# Daughter_Card_v7_fixed.net
KiCad netlist of a schematic drawn in EAGLE
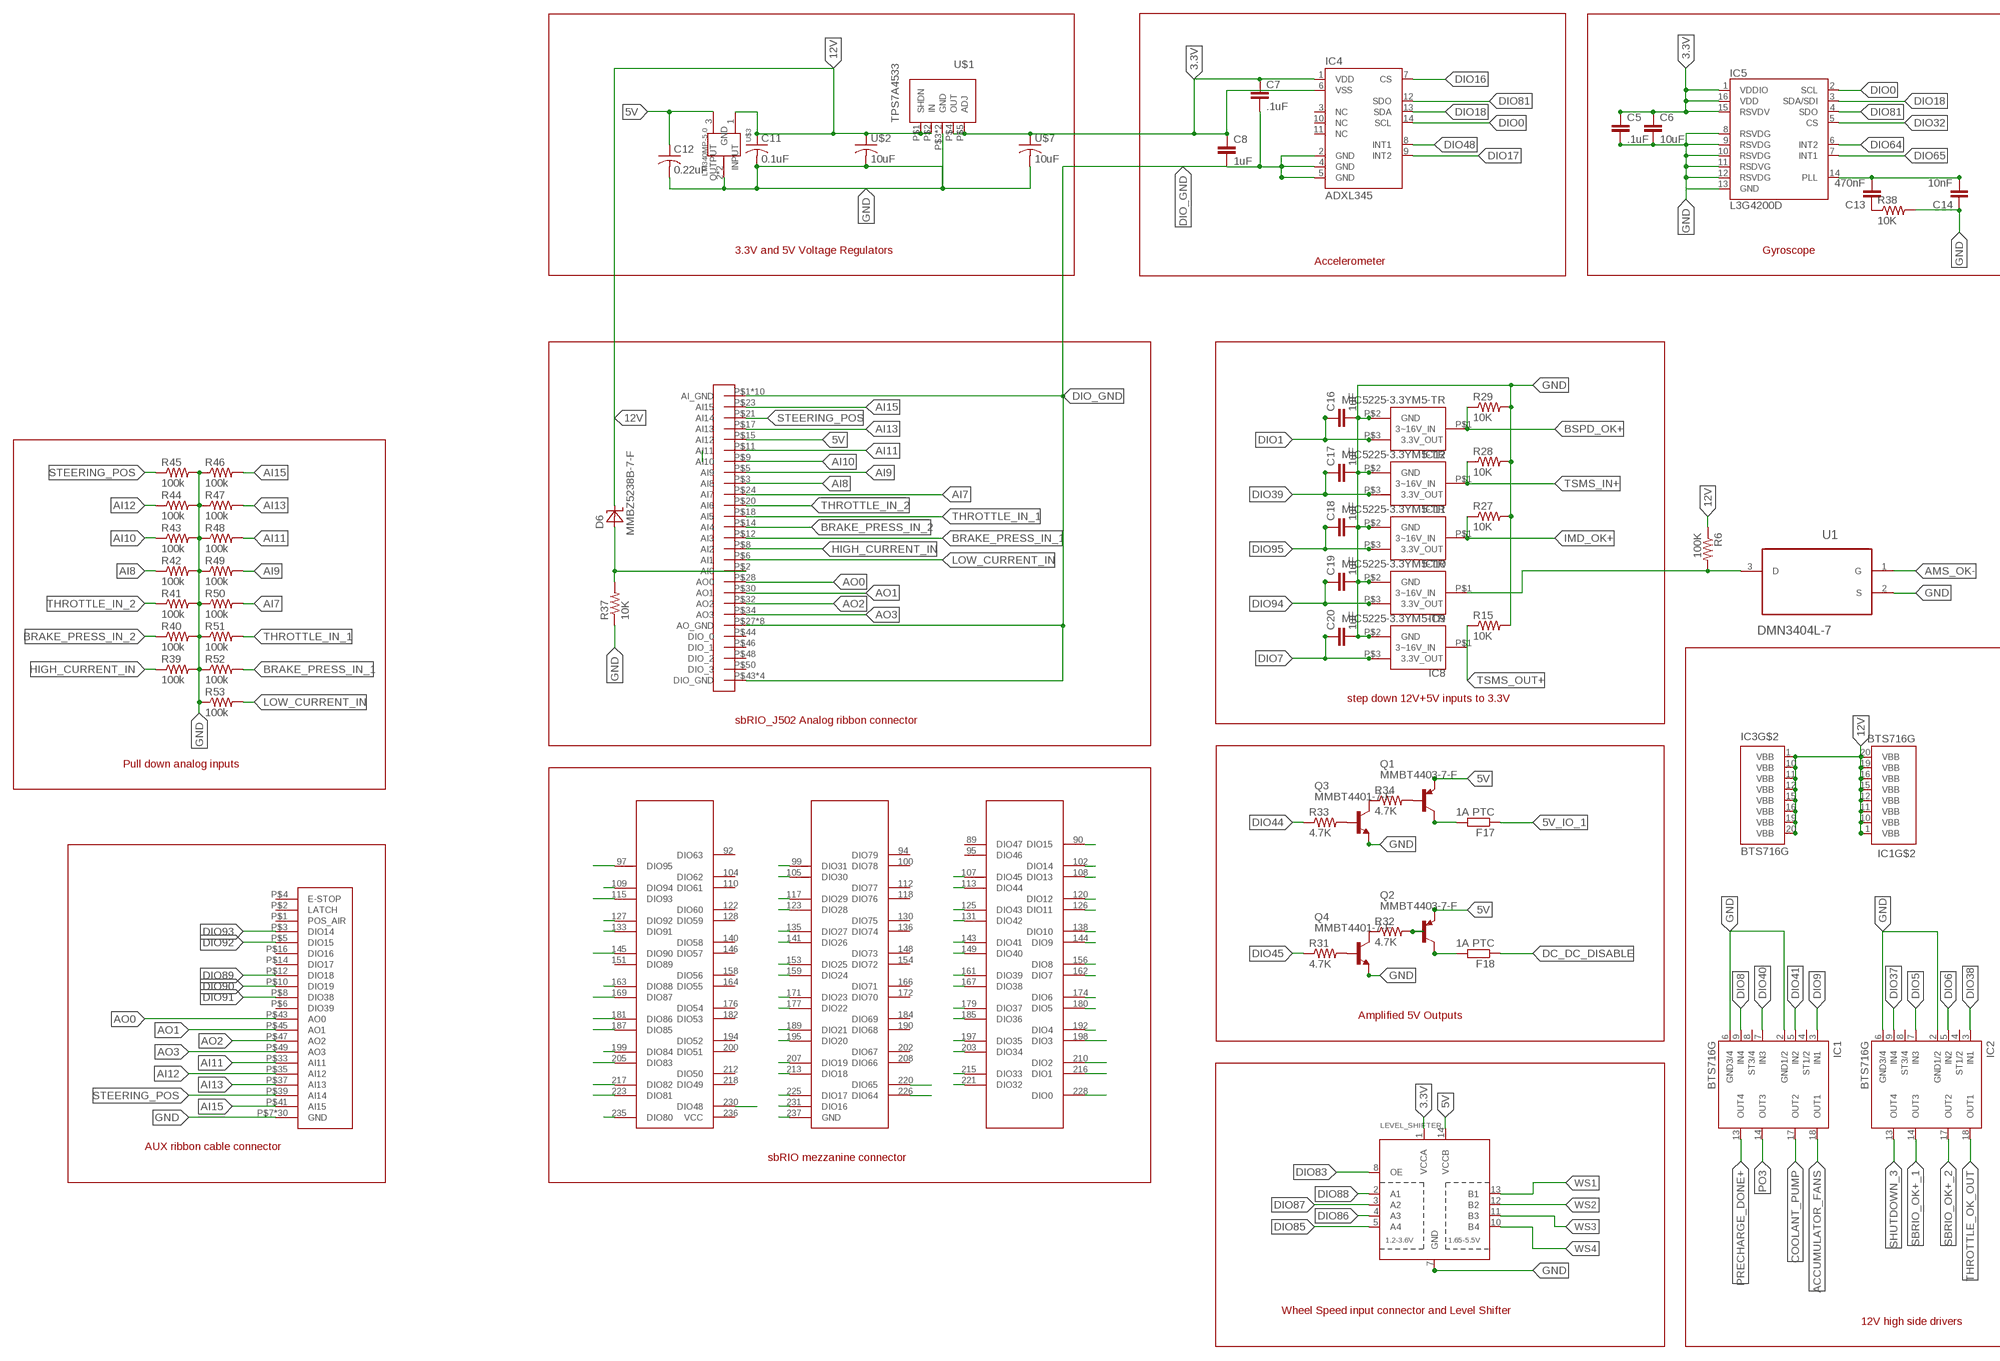
[diagram p0: schematic, sheet 1, part 1 of 2]
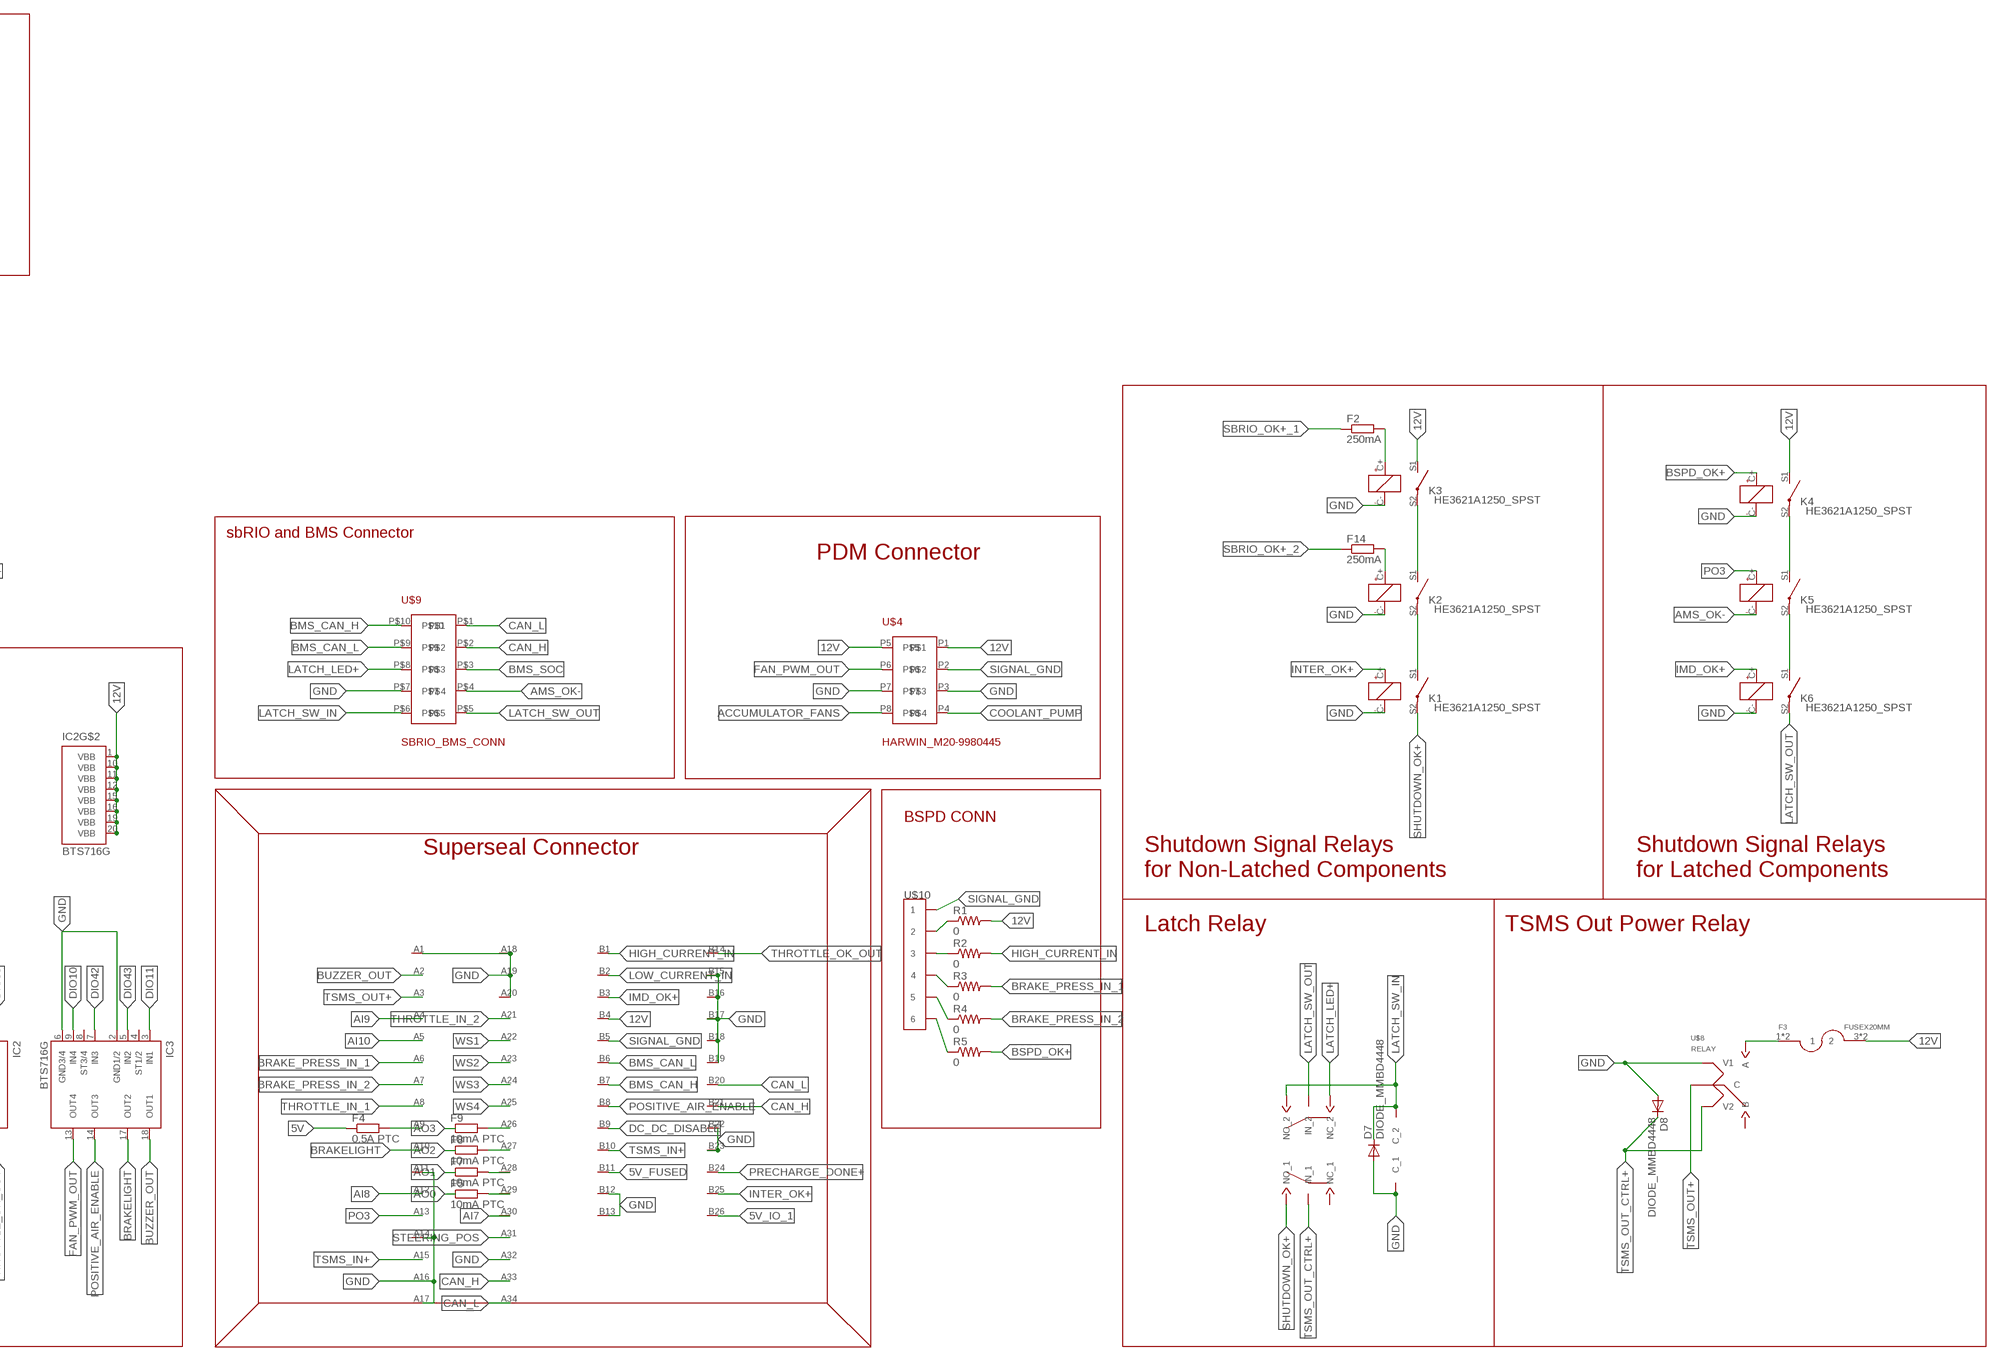
[diagram p1: schematic, sheet 1, part 2 of 2]

(export (version "E")
  (design (tool "Eeschema 10.0.6"))
  (components
    (comp (ref "C5")
      (value ".1uF")
      (footprint "eagle-import:0603-CAP")
      (libsource (lib "eagle-import") (part "CAP0603-CAP"))
    )
    (comp (ref "C6")
      (value "10uF")
      (footprint "eagle-import:0603-CAP")
      (libsource (lib "eagle-import") (part "CAP0603-CAP"))
    )
    (comp (ref "C7")
      (value ".1uF")
      (footprint "eagle-import:0603-CAP")
      (libsource (lib "eagle-import") (part "CAP0603-CAP"))
    )
    (comp (ref "C8")
      (value "1uF")
      (footprint "eagle-import:0603-CAP")
      (libsource (lib "eagle-import") (part "CAP0603-CAP"))
    )
    (comp (ref "C11")
      (value "0.1uF")
      (footprint "eagle-import:C1206")
      (libsource (lib "eagle-import") (part "C-USC1206"))
    )
    (comp (ref "C12")
      (value "0.22uF")
      (footprint "eagle-import:C1206")
      (libsource (lib "eagle-import") (part "C-USC1206"))
    )
    (comp (ref "C13")
      (value "470nF")
      (footprint "eagle-import:0603-CAP")
      (libsource (lib "eagle-import") (part "CAP0603-CAP"))
    )
    (comp (ref "C14")
      (value "10nF")
      (footprint "eagle-import:0603-CAP")
      (libsource (lib "eagle-import") (part "CAP0603-CAP"))
    )
    (comp (ref "C16")
      (value "1uF")
      (footprint "eagle-import:0603-CAP")
      (libsource (lib "eagle-import") (part "CAP0603-CAP"))
    )
    (comp (ref "C17")
      (value "1uF")
      (footprint "eagle-import:0603-CAP")
      (libsource (lib "eagle-import") (part "CAP0603-CAP"))
    )
    (comp (ref "C18")
      (value "1uF")
      (footprint "eagle-import:0603-CAP")
      (libsource (lib "eagle-import") (part "CAP0603-CAP"))
    )
    (comp (ref "C19")
      (value "1uF")
      (footprint "eagle-import:0603-CAP")
      (libsource (lib "eagle-import") (part "CAP0603-CAP"))
    )
    (comp (ref "C20")
      (value "1uF")
      (footprint "eagle-import:0603-CAP")
      (libsource (lib "eagle-import") (part "CAP0603-CAP"))
    )
    (comp (ref "D6")
      (value "MMBZ5238B-7-F")
      (footprint "eagle-import:SOT-23-3")
      (libsource (lib "eagle-import") (part "MMBZ5238B-7-F"))
    )
    (comp (ref "D7")
      (value "DIODE_MMBD4448")
      (footprint "eagle-import:SOT-23-3")
      (libsource (lib "eagle-import") (part "DIODE_MMBD4448"))
    )
    (comp (ref "D8")
      (value "DIODE_MMBD4448")
      (footprint "eagle-import:SOT-23-3")
      (libsource (lib "eagle-import") (part "DIODE_MMBD4448"))
    )
    (comp (ref "F2")
      (value "250mA")
      (footprint "eagle-import:R0603")
      (libsource (lib "eagle-import") (part "R-EU_R0603"))
    )
    (comp (ref "F3")
      (value "FUSEX20MM")
      (footprint "eagle-import:FUSE_5MM")
      (libsource (lib "eagle-import") (part "FUSEX20MM"))
    )
    (comp (ref "F4")
      (value "0.5A PTC")
      (footprint "eagle-import:R0603")
      (libsource (lib "eagle-import") (part "R-EU_R0603"))
    )
    (comp (ref "F5")
      (value "10mA PTC")
      (footprint "eagle-import:R0603")
      (libsource (lib "eagle-import") (part "R-EU_R0603"))
    )
    (comp (ref "F7")
      (value "10mA PTC")
      (footprint "eagle-import:R0603")
      (libsource (lib "eagle-import") (part "R-EU_R0603"))
    )
    (comp (ref "F8")
      (value "10mA PTC")
      (footprint "eagle-import:R0603")
      (libsource (lib "eagle-import") (part "R-EU_R0603"))
    )
    (comp (ref "F9")
      (value "10mA PTC")
      (footprint "eagle-import:R0603")
      (libsource (lib "eagle-import") (part "R-EU_R0603"))
    )
    (comp (ref "F14")
      (value "250mA")
      (footprint "eagle-import:R0603")
      (libsource (lib "eagle-import") (part "R-EU_R0603"))
    )
    (comp (ref "F17")
      (value "1A PTC")
      (footprint "eagle-import:R0603")
      (libsource (lib "eagle-import") (part "R-EU_R0603"))
    )
    (comp (ref "F18")
      (value "1A PTC")
      (footprint "eagle-import:R0603")
      (libsource (lib "eagle-import") (part "R-EU_R0603"))
    )
    (comp (ref "IC1")
      (value "BTS716G")
      (footprint "eagle-import:PG-DSO-20")
      (libsource (lib "eagle-import") (part "BTS716G"))
    )
    (comp (ref "IC2")
      (value "BTS716G")
      (footprint "eagle-import:PG-DSO-20")
      (libsource (lib "eagle-import") (part "BTS716G"))
    )
    (comp (ref "IC3")
      (value "BTS716G")
      (footprint "eagle-import:PG-DSO-20")
      (libsource (lib "eagle-import") (part "BTS716G"))
    )
    (comp (ref "IC4")
      (value "ADXL345")
      (footprint "eagle-import:LGA14")
      (libsource (lib "eagle-import") (part "ADXL345"))
    )
    (comp (ref "IC5")
      (value "L3G4200D")
      (footprint "eagle-import:LGA16-4X4")
      (libsource (lib "eagle-import") (part "L3G4200D"))
    )
    (comp (ref "IC8")
      (value "MIC5225-3.3YM5-TR")
      (footprint "eagle-import:SOT-23-3")
      (libsource (lib "eagle-import") (part "MIC5225-3.3YM5-TR"))
    )
    (comp (ref "IC9")
      (value "MIC5225-3.3YM5-TR")
      (footprint "eagle-import:SOT-23-3")
      (libsource (lib "eagle-import") (part "MIC5225-3.3YM5-TR"))
    )
    (comp (ref "IC10")
      (value "MIC5225-3.3YM5-TR")
      (footprint "eagle-import:SOT-23-3")
      (libsource (lib "eagle-import") (part "MIC5225-3.3YM5-TR"))
    )
    (comp (ref "IC11")
      (value "MIC5225-3.3YM5-TR")
      (footprint "eagle-import:SOT-23-3")
      (libsource (lib "eagle-import") (part "MIC5225-3.3YM5-TR"))
    )
    (comp (ref "IC12")
      (value "MIC5225-3.3YM5-TR")
      (footprint "eagle-import:SOT-23-3")
      (libsource (lib "eagle-import") (part "MIC5225-3.3YM5-TR"))
    )
    (comp (ref "K1")
      (value "HE3621A1250_SPST")
      (footprint "eagle-import:HE3621A1250_SPST")
      (libsource (lib "eagle-import") (part "HE3621A1250_SPST"))
    )
    (comp (ref "K2")
      (value "HE3621A1250_SPST")
      (footprint "eagle-import:HE3621A1250_SPST")
      (libsource (lib "eagle-import") (part "HE3621A1250_SPST"))
    )
    (comp (ref "K3")
      (value "HE3621A1250_SPST")
      (footprint "eagle-import:HE3621A1250_SPST")
      (libsource (lib "eagle-import") (part "HE3621A1250_SPST"))
    )
    (comp (ref "K4")
      (value "HE3621A1250_SPST")
      (footprint "eagle-import:HE3621A1250_SPST")
      (libsource (lib "eagle-import") (part "HE3621A1250_SPST"))
    )
    (comp (ref "K5")
      (value "HE3621A1250_SPST")
      (footprint "eagle-import:HE3621A1250_SPST")
      (libsource (lib "eagle-import") (part "HE3621A1250_SPST"))
    )
    (comp (ref "K6")
      (value "HE3621A1250_SPST")
      (footprint "eagle-import:HE3621A1250_SPST")
      (libsource (lib "eagle-import") (part "HE3621A1250_SPST"))
    )
    (comp (ref "LATCH_U7")
      (value "JW2SN-DC12V")
      (footprint "eagle-import:DPDT_JW2_FORM_C")
      (libsource (lib "eagle-import") (part "JW2SN-DC12V"))
    )
    (comp (ref "LEVEL_SHIFTER")
      (value "TXB0104PWR")
      (footprint "eagle-import:TSSOP14")
      (libsource (lib "eagle-import") (part "TXB0104PWR"))
    )
    (comp (ref "Q1")
      (value "MMBT4403-7-F")
      (footprint "eagle-import:SOT-23-3")
      (libsource (lib "eagle-import") (part "MMBT4403-7-F"))
    )
    (comp (ref "Q2")
      (value "MMBT4403-7-F")
      (footprint "eagle-import:SOT-23-3")
      (libsource (lib "eagle-import") (part "MMBT4403-7-F"))
    )
    (comp (ref "Q3")
      (value "MMBT4401-7-F")
      (footprint "eagle-import:SOT-23-3")
      (libsource (lib "eagle-import") (part "MMBT4401-7-F"))
    )
    (comp (ref "Q4")
      (value "MMBT4401-7-F")
      (footprint "eagle-import:SOT-23-3")
      (libsource (lib "eagle-import") (part "MMBT4401-7-F"))
    )
    (comp (ref "R1")
      (value "0")
      (footprint "eagle-import:M0805")
      (libsource (lib "eagle-import") (part "resistor_R-US_M0805"))
    )
    (comp (ref "R2")
      (value "0")
      (footprint "eagle-import:M0805")
      (libsource (lib "eagle-import") (part "resistor_R-US_M0805"))
    )
    (comp (ref "R3")
      (value "0")
      (footprint "eagle-import:M0805")
      (libsource (lib "eagle-import") (part "resistor_R-US_M0805"))
    )
    (comp (ref "R4")
      (value "0")
      (footprint "eagle-import:M0805")
      (libsource (lib "eagle-import") (part "resistor_R-US_M0805"))
    )
    (comp (ref "R5")
      (value "0")
      (footprint "eagle-import:M0805")
      (libsource (lib "eagle-import") (part "resistor_R-US_M0805"))
    )
    (comp (ref "R6")
      (value "100K")
      (footprint "eagle-import:R0603")
      (libsource (lib "eagle-import") (part "R-US_R0603"))
    )
    (comp (ref "R15")
      (value "10K")
      (footprint "eagle-import:R0603")
      (libsource (lib "eagle-import") (part "resistor_R-US_R0603"))
    )
    (comp (ref "R27")
      (value "10K")
      (footprint "eagle-import:R0603")
      (libsource (lib "eagle-import") (part "resistor_R-US_R0603"))
    )
    (comp (ref "R28")
      (value "10K")
      (footprint "eagle-import:R0603")
      (libsource (lib "eagle-import") (part "resistor_R-US_R0603"))
    )
    (comp (ref "R29")
      (value "10K")
      (footprint "eagle-import:R0603")
      (libsource (lib "eagle-import") (part "resistor_R-US_R0603"))
    )
    (comp (ref "R31")
      (value "4.7K")
      (footprint "eagle-import:R0603")
      (libsource (lib "eagle-import") (part "resistor_R-US_R0603"))
    )
    (comp (ref "R32")
      (value "4.7K")
      (footprint "eagle-import:R0603")
      (libsource (lib "eagle-import") (part "resistor_R-US_R0603"))
    )
    (comp (ref "R33")
      (value "4.7K")
      (footprint "eagle-import:R0603")
      (libsource (lib "eagle-import") (part "resistor_R-US_R0603"))
    )
    (comp (ref "R34")
      (value "4.7K")
      (footprint "eagle-import:R0603")
      (libsource (lib "eagle-import") (part "resistor_R-US_R0603"))
    )
    (comp (ref "R37")
      (value "10K")
      (footprint "eagle-import:R0603")
      (libsource (lib "eagle-import") (part "resistor_R-US_R0603"))
    )
    (comp (ref "R38")
      (value "10K")
      (footprint "eagle-import:R0603")
      (libsource (lib "eagle-import") (part "resistor_R-US_R0603"))
    )
    (comp (ref "R39")
      (value "100k")
      (footprint "eagle-import:R0603")
      (libsource (lib "eagle-import") (part "resistor_R-US_R0603"))
    )
    (comp (ref "R40")
      (value "100k")
      (footprint "eagle-import:R0603")
      (libsource (lib "eagle-import") (part "resistor_R-US_R0603"))
    )
    (comp (ref "R41")
      (value "100k")
      (footprint "eagle-import:R0603")
      (libsource (lib "eagle-import") (part "resistor_R-US_R0603"))
    )
    (comp (ref "R42")
      (value "100k")
      (footprint "eagle-import:R0603")
      (libsource (lib "eagle-import") (part "resistor_R-US_R0603"))
    )
    (comp (ref "R43")
      (value "100k")
      (footprint "eagle-import:R0603")
      (libsource (lib "eagle-import") (part "resistor_R-US_R0603"))
    )
    (comp (ref "R44")
      (value "100k")
      (footprint "eagle-import:R0603")
      (libsource (lib "eagle-import") (part "resistor_R-US_R0603"))
    )
    (comp (ref "R45")
      (value "100k")
      (footprint "eagle-import:R0603")
      (libsource (lib "eagle-import") (part "resistor_R-US_R0603"))
    )
    (comp (ref "R46")
      (value "100k")
      (footprint "eagle-import:R0603")
      (libsource (lib "eagle-import") (part "resistor_R-US_R0603"))
    )
    (comp (ref "R47")
      (value "100k")
      (footprint "eagle-import:R0603")
      (libsource (lib "eagle-import") (part "resistor_R-US_R0603"))
    )
    (comp (ref "R48")
      (value "100k")
      (footprint "eagle-import:R0603")
      (libsource (lib "eagle-import") (part "resistor_R-US_R0603"))
    )
    (comp (ref "R49")
      (value "100k")
      (footprint "eagle-import:R0603")
      (libsource (lib "eagle-import") (part "resistor_R-US_R0603"))
    )
    (comp (ref "R50")
      (value "100k")
      (footprint "eagle-import:R0603")
      (libsource (lib "eagle-import") (part "resistor_R-US_R0603"))
    )
    (comp (ref "R51")
      (value "100k")
      (footprint "eagle-import:R0603")
      (libsource (lib "eagle-import") (part "resistor_R-US_R0603"))
    )
    (comp (ref "R52")
      (value "100k")
      (footprint "eagle-import:R0603")
      (libsource (lib "eagle-import") (part "resistor_R-US_R0603"))
    )
    (comp (ref "R53")
      (value "100k")
      (footprint "eagle-import:R0603")
      (libsource (lib "eagle-import") (part "resistor_R-US_R0603"))
    )
    (comp (ref "SBRIO_ANALOG")
      (value "SBRIO_MIO")
      (footprint "eagle-import:SBRIO_J502_J503")
      (libsource (lib "eagle-import") (part "SBRIO_MIO"))
    )
    (comp (ref "SBRIO_AUX")
      (value "SBRIO_AUX")
      (footprint "eagle-import:SBRIO_J502_J503")
      (libsource (lib "eagle-import") (part "SBRIO_AUX"))
    )
    (comp (ref "SBRIO_MEZZANINE")
      (value "SBRIO_RMC")
      (footprint "eagle-import:SEAM-40-XX.X-XX-06-X-A")
      (libsource (lib "eagle-import") (part "SBRIO_RMC"))
    )
    (comp (ref "U$1")
      (value "TPS7A4533")
      (footprint "eagle-import:TPS7A4533")
      (libsource (lib "eagle-import") (part "TPS7A4533"))
    )
    (comp (ref "U$2")
      (value "10uF")
      (footprint "eagle-import:C1206")
      (libsource (lib "eagle-import") (part "C-USC1206"))
    )
    (comp (ref "U$3")
      (value "LM340MP-5.0")
      (footprint "eagle-import:SOT-223-4")
      (libsource (lib "eagle-import") (part "LM340MP-5.0"))
    )
    (comp (ref "U$4")
      (value "HARWIN_M20-9980445")
      (footprint "eagle-import:HARWIN_M20-9980445")
      (libsource (lib "eagle-import") (part "HARWIN_M20-9980445"))
    )
    (comp (ref "U$6")
      (value "SUPERSEAL1.0_60POS")
      (footprint "eagle-import:SUPERSEAL1.0_60POS")
      (libsource (lib "eagle-import") (part "SUPERSEAL1.0_60POS"))
    )
    (comp (ref "U$7")
      (value "10uF")
      (footprint "eagle-import:C1206")
      (libsource (lib "eagle-import") (part "C-USC1206"))
    )
    (comp (ref "U$8")
      (value "RELAY")
      (footprint "eagle-import:RELAY")
      (libsource (lib "eagle-import") (part "RELAY"))
    )
    (comp (ref "U$9")
      (value "SBRIO_BMS_CONN")
      (footprint "eagle-import:SBRIO_W")
      (libsource (lib "eagle-import") (part "SBRIO_BMS_CONN"))
    )
    (comp (ref "U$10")
      (value "SULLINS_1MM_6P_HEADER")
      (footprint "eagle-import:SULLINS_1MM_HEADER")
      (libsource (lib "eagle-import") (part "SULLINS_1MM_6P_HEADER"))
    )
    (comp (ref "U1")
      (value "DMN3404L-7")
      (footprint "eagle-import:SOT95P235X112-3N")
      (libsource (lib "eagle-import") (part "DMN3404L-7"))
    )
  )
  (nets
    (net (code "1") (name "/VCC") (class "Default")
      (node (ref "SBRIO_MEZZANINE") (pin "236") (pinfunction "VCC_236") (pintype "power_in"))
    )
    (net (code "2") (name "3.3V") (class "Default")
      (node (ref "C5") (pin "1") (pinfunction "1_1") (pintype "passive"))
      (node (ref "C6") (pin "1") (pinfunction "1_1") (pintype "passive"))
      (node (ref "C7") (pin "1") (pinfunction "1_1") (pintype "passive"))
      (node (ref "C8") (pin "1") (pinfunction "1_1") (pintype "passive"))
      (node (ref "IC4") (pin "1") (pinfunction "VDD_1") (pintype "bidirectional"))
      (node (ref "IC4") (pin "6") (pinfunction "VSS_6") (pintype "bidirectional"))
      (node (ref "IC5") (pin "1") (pinfunction "VDDIO_1") (pintype "bidirectional"))
      (node (ref "IC5") (pin "15") (pinfunction "RSVDV_15") (pintype "bidirectional"))
      (node (ref "IC5") (pin "16") (pinfunction "VDD_16") (pintype "bidirectional"))
      (node (ref "LEVEL_SHIFTER") (pin "1") (pinfunction "VCCA_1") (pintype "bidirectional"))
      (node (ref "U$1") (pin "P$4") (pinfunction "OUT_P$4") (pintype "bidirectional"))
      (node (ref "U$1") (pin "P$5") (pinfunction "ADJ_P$5") (pintype "bidirectional"))
      (node (ref "U$7") (pin "1") (pinfunction "1_1") (pintype "passive"))
    )
    (net (code "3") (name "5V") (class "Default")
      (node (ref "C12") (pin "1") (pinfunction "1_1") (pintype "passive"))
      (node (ref "F4") (pin "1") (pinfunction "1_1") (pintype "passive"))
      (node (ref "LEVEL_SHIFTER") (pin "14") (pinfunction "VCCB_14") (pintype "bidirectional"))
      (node (ref "Q1") (pin "P$3") (pinfunction "E_P$3") (pintype "passive"))
      (node (ref "Q2") (pin "P$3") (pinfunction "E_P$3") (pintype "passive"))
      (node (ref "SBRIO_ANALOG") (pin "P$15") (pinfunction "AI12_P$15") (pintype "input"))
      (node (ref "U$3") (pin "3") (pinfunction "OUTPUT_3") (pintype "bidirectional"))
    )
    (net (code "4") (name "5V_FUSED") (class "Default")
      (node (ref "F4") (pin "2") (pinfunction "2_2") (pintype "passive"))
      (node (ref "U$6") (pin "A9") (pinfunction "A9_A9") (pintype "bidirectional"))
      (node (ref "U$6") (pin "B11") (pinfunction "B11_B11") (pintype "bidirectional"))
    )
    (net (code "5") (name "5V_IO_1") (class "Default")
      (node (ref "F17") (pin "1") (pinfunction "1_1") (pintype "passive"))
      (node (ref "U$6") (pin "B26") (pinfunction "B26_B26") (pintype "bidirectional"))
    )
    (net (code "6") (name "12V") (class "Default")
      (node (ref "C11") (pin "1") (pinfunction "1_1") (pintype "passive"))
      (node (ref "D6") (pin "P$1") (pinfunction "C_P$1") (pintype "passive"))
      (node (ref "F3") (pin "3") (pinfunction "2_3") (pintype "bidirectional"))
      (node (ref "F3") (pin "4") (pinfunction "2_4") (pintype "bidirectional"))
      (node (ref "IC1") (pin "1") (pinfunction "VBB_1") (pintype "power_in"))
      (node (ref "IC1") (pin "10") (pinfunction "VBB_10") (pintype "power_in"))
      (node (ref "IC1") (pin "11") (pinfunction "VBB_11") (pintype "power_in"))
      (node (ref "IC1") (pin "12") (pinfunction "VBB_12") (pintype "power_in"))
      (node (ref "IC1") (pin "15") (pinfunction "VBB_15") (pintype "power_in"))
      (node (ref "IC1") (pin "16") (pinfunction "VBB_16") (pintype "power_in"))
      (node (ref "IC1") (pin "19") (pinfunction "VBB_19") (pintype "power_in"))
      (node (ref "IC1") (pin "20") (pinfunction "VBB_20") (pintype "power_in"))
      (node (ref "IC2") (pin "1") (pinfunction "VBB_1") (pintype "power_in"))
      (node (ref "IC2") (pin "10") (pinfunction "VBB_10") (pintype "power_in"))
      (node (ref "IC2") (pin "11") (pinfunction "VBB_11") (pintype "power_in"))
      (node (ref "IC2") (pin "12") (pinfunction "VBB_12") (pintype "power_in"))
      (node (ref "IC2") (pin "15") (pinfunction "VBB_15") (pintype "power_in"))
      (node (ref "IC2") (pin "16") (pinfunction "VBB_16") (pintype "power_in"))
      (node (ref "IC2") (pin "19") (pinfunction "VBB_19") (pintype "power_in"))
      (node (ref "IC2") (pin "20") (pinfunction "VBB_20") (pintype "power_in"))
      (node (ref "IC3") (pin "1") (pinfunction "VBB_1") (pintype "power_in"))
      (node (ref "IC3") (pin "10") (pinfunction "VBB_10") (pintype "power_in"))
      (node (ref "IC3") (pin "11") (pinfunction "VBB_11") (pintype "power_in"))
      (node (ref "IC3") (pin "12") (pinfunction "VBB_12") (pintype "power_in"))
      (node (ref "IC3") (pin "15") (pinfunction "VBB_15") (pintype "power_in"))
      (node (ref "IC3") (pin "16") (pinfunction "VBB_16") (pintype "power_in"))
      (node (ref "IC3") (pin "19") (pinfunction "VBB_19") (pintype "power_in"))
      (node (ref "IC3") (pin "20") (pinfunction "VBB_20") (pintype "power_in"))
      (node (ref "K3") (pin "S1") (pinfunction "SW_1_S1") (pintype "passive"))
      (node (ref "K4") (pin "S1") (pinfunction "SW_1_S1") (pintype "passive"))
      (node (ref "R1") (pin "2") (pinfunction "2_2") (pintype "passive"))
      (node (ref "R6") (pin "1") (pinfunction "1_1") (pintype "passive"))
      (node (ref "U$1") (pin "P$1") (pinfunction "SHDN_P$1") (pintype "bidirectional"))
      (node (ref "U$1") (pin "P$2") (pinfunction "IN_P$2") (pintype "bidirectional"))
      (node (ref "U$2") (pin "1") (pinfunction "1_1") (pintype "passive"))
      (node (ref "U$3") (pin "1") (pinfunction "INPUT_1") (pintype "bidirectional"))
      (node (ref "U$4") (pin "P1") (pinfunction "P$1_P1") (pintype "bidirectional"))
      (node (ref "U$4") (pin "P5") (pinfunction "P$5_P5") (pintype "bidirectional"))
      (node (ref "U$6") (pin "B4") (pinfunction "B4_B4") (pintype "bidirectional"))
    )
    (net (code "7") (name "ACCUMULATOR_FANS") (class "Default")
      (node (ref "IC1") (pin "18") (pinfunction "OUT1_18") (pintype "output"))
      (node (ref "U$4") (pin "P8") (pinfunction "P$8_P8") (pintype "bidirectional"))
    )
    (net (code "8") (name "AI7") (class "Default")
      (node (ref "R50") (pin "2") (pinfunction "2_2") (pintype "passive"))
      (node (ref "SBRIO_ANALOG") (pin "P$24") (pinfunction "AI7_P$24") (pintype "input"))
      (node (ref "U$6") (pin "A30") (pinfunction "A30_A30") (pintype "bidirectional"))
    )
    (net (code "9") (name "AI8") (class "Default")
      (node (ref "R42") (pin "1") (pinfunction "1_1") (pintype "passive"))
      (node (ref "SBRIO_ANALOG") (pin "P$3") (pinfunction "AI8_P$3") (pintype "input"))
      (node (ref "U$6") (pin "A12") (pinfunction "A12_A12") (pintype "bidirectional"))
    )
    (net (code "10") (name "AI9") (class "Default")
      (node (ref "R49") (pin "2") (pinfunction "2_2") (pintype "passive"))
      (node (ref "SBRIO_ANALOG") (pin "P$5") (pinfunction "AI9_P$5") (pintype "input"))
      (node (ref "U$6") (pin "A4") (pinfunction "A4_A4") (pintype "bidirectional"))
    )
    (net (code "11") (name "AI10") (class "Default")
      (node (ref "R43") (pin "1") (pinfunction "1_1") (pintype "passive"))
      (node (ref "SBRIO_ANALOG") (pin "P$9") (pinfunction "AI10_P$9") (pintype "input"))
      (node (ref "U$6") (pin "A5") (pinfunction "A5_A5") (pintype "bidirectional"))
    )
    (net (code "12") (name "AI11") (class "Default")
      (node (ref "R48") (pin "2") (pinfunction "2_2") (pintype "passive"))
      (node (ref "SBRIO_ANALOG") (pin "P$11") (pinfunction "AI11_P$11") (pintype "input"))
      (node (ref "SBRIO_AUX") (pin "P$33") (pinfunction "AI11_P$33") (pintype "bidirectional"))
    )
    (net (code "13") (name "AI12") (class "Default")
      (node (ref "R44") (pin "1") (pinfunction "1_1") (pintype "passive"))
      (node (ref "SBRIO_AUX") (pin "P$35") (pinfunction "AI12_P$35") (pintype "bidirectional"))
    )
    (net (code "14") (name "AI13") (class "Default")
      (node (ref "R47") (pin "2") (pinfunction "2_2") (pintype "passive"))
      (node (ref "SBRIO_ANALOG") (pin "P$17") (pinfunction "AI13_P$17") (pintype "input"))
      (node (ref "SBRIO_AUX") (pin "P$37") (pinfunction "AI13_P$37") (pintype "bidirectional"))
    )
    (net (code "15") (name "AI15") (class "Default")
      (node (ref "R46") (pin "2") (pinfunction "2_2") (pintype "passive"))
      (node (ref "SBRIO_ANALOG") (pin "P$23") (pinfunction "AI15_P$23") (pintype "input"))
      (node (ref "SBRIO_AUX") (pin "P$41") (pinfunction "AI15_P$41") (pintype "bidirectional"))
    )
    (net (code "16") (name "AMS_OK-") (class "Default")
      (node (ref "K5") (pin "C-") (pinfunction "C-_C-") (pintype "passive"))
      (node (ref "U$9") (pin "P$4") (pinfunction "P$4_P$4") (pintype "bidirectional"))
      (node (ref "U1") (pin "1") (pinfunction "G_1") (pintype "input"))
    )
    (net (code "17") (name "AO0") (class "Default")
      (node (ref "F5") (pin "1") (pinfunction "1_1") (pintype "passive"))
      (node (ref "SBRIO_ANALOG") (pin "P$28") (pinfunction "AO0_P$28") (pintype "output"))
      (node (ref "SBRIO_AUX") (pin "P$43") (pinfunction "AO0_P$43") (pintype "bidirectional"))
    )
    (net (code "18") (name "AO1") (class "Default")
      (node (ref "F7") (pin "1") (pinfunction "1_1") (pintype "passive"))
      (node (ref "SBRIO_ANALOG") (pin "P$30") (pinfunction "AO1_P$30") (pintype "output"))
      (node (ref "SBRIO_AUX") (pin "P$45") (pinfunction "AO1_P$45") (pintype "bidirectional"))
    )
    (net (code "19") (name "AO2") (class "Default")
      (node (ref "F8") (pin "1") (pinfunction "1_1") (pintype "passive"))
      (node (ref "SBRIO_ANALOG") (pin "P$32") (pinfunction "AO2_P$32") (pintype "output"))
      (node (ref "SBRIO_AUX") (pin "P$47") (pinfunction "AO2_P$47") (pintype "bidirectional"))
    )
    (net (code "20") (name "AO3") (class "Default")
      (node (ref "F9") (pin "1") (pinfunction "1_1") (pintype "passive"))
      (node (ref "SBRIO_ANALOG") (pin "P$34") (pinfunction "AO3_P$34") (pintype "output"))
      (node (ref "SBRIO_AUX") (pin "P$49") (pinfunction "AO3_P$49") (pintype "bidirectional"))
    )
    (net (code "21") (name "BMS_CAN_H") (class "Default")
      (node (ref "U$6") (pin "B7") (pinfunction "B7_B7") (pintype "bidirectional"))
      (node (ref "U$9") (pin "P$10") (pinfunction "P$10_P$10") (pintype "bidirectional"))
    )
    (net (code "22") (name "BMS_CAN_L") (class "Default")
      (node (ref "U$6") (pin "B6") (pinfunction "B6_B6") (pintype "bidirectional"))
      (node (ref "U$9") (pin "P$9") (pinfunction "P$9_P$9") (pintype "bidirectional"))
    )
    (net (code "23") (name "BMS_SOC") (class "Default")
      (node (ref "U$9") (pin "P$3") (pinfunction "P$3_P$3") (pintype "bidirectional"))
    )
    (net (code "24") (name "BRAKELIGHT") (class "Default")
      (node (ref "IC3") (pin "17") (pinfunction "OUT2_17") (pintype "output"))
      (node (ref "U$6") (pin "A10") (pinfunction "A10_A10") (pintype "bidirectional"))
    )
    (net (code "25") (name "BRAKE_PRESS_IN_1") (class "Default")
      (node (ref "R3") (pin "2") (pinfunction "2_2") (pintype "passive"))
      (node (ref "R52") (pin "2") (pinfunction "2_2") (pintype "passive"))
      (node (ref "SBRIO_ANALOG") (pin "P$12") (pinfunction "AI3_P$12") (pintype "input"))
      (node (ref "U$6") (pin "A6") (pinfunction "A6_A6") (pintype "bidirectional"))
    )
    (net (code "26") (name "BRAKE_PRESS_IN_2") (class "Default")
      (node (ref "R4") (pin "2") (pinfunction "2_2") (pintype "passive"))
      (node (ref "R40") (pin "1") (pinfunction "1_1") (pintype "passive"))
      (node (ref "SBRIO_ANALOG") (pin "P$14") (pinfunction "AI4_P$14") (pintype "input"))
      (node (ref "U$6") (pin "A7") (pinfunction "A7_A7") (pintype "bidirectional"))
    )
    (net (code "27") (name "BSPD_OK+") (class "Default")
      (node (ref "IC12") (pin "P$1") (pinfunction "3~{16V_IN}_P$1") (pintype "bidirectional"))
      (node (ref "K4") (pin "C+") (pinfunction "C+_C+") (pintype "passive"))
      (node (ref "R29") (pin "1") (pinfunction "1_1") (pintype "passive"))
      (node (ref "R5") (pin "2") (pinfunction "2_2") (pintype "passive"))
    )
    (net (code "28") (name "BUZZER_OUT") (class "Default")
      (node (ref "IC3") (pin "18") (pinfunction "OUT1_18") (pintype "output"))
      (node (ref "U$6") (pin "A2") (pinfunction "A2_A2") (pintype "bidirectional"))
    )
    (net (code "29") (name "CAN_H") (class "Default")
      (node (ref "U$6") (pin "A33") (pinfunction "A33_A33") (pintype "bidirectional"))
      (node (ref "U$6") (pin "B21") (pinfunction "B21_B21") (pintype "bidirectional"))
      (node (ref "U$9") (pin "P$2") (pinfunction "P$2_P$2") (pintype "bidirectional"))
    )
    (net (code "30") (name "CAN_L") (class "Default")
      (node (ref "U$6") (pin "A34") (pinfunction "A34_A34") (pintype "bidirectional"))
      (node (ref "U$6") (pin "B20") (pinfunction "B20_B20") (pintype "bidirectional"))
      (node (ref "U$9") (pin "P$1") (pinfunction "P$1_P$1") (pintype "bidirectional"))
    )
    (net (code "31") (name "COOLANT_PUMP") (class "Default")
      (node (ref "IC1") (pin "17") (pinfunction "OUT2_17") (pintype "output"))
      (node (ref "U$4") (pin "P4") (pinfunction "P$4_P4") (pintype "bidirectional"))
    )
    (net (code "32") (name "DC_DC_DISABLE") (class "Default")
      (node (ref "F18") (pin "1") (pinfunction "1_1") (pintype "passive"))
      (node (ref "U$6") (pin "B9") (pinfunction "B9_B9") (pintype "bidirectional"))
    )
    (net (code "33") (name "DIO0") (class "Default")
      (node (ref "IC4") (pin "14") (pinfunction "SCL_14") (pintype "bidirectional"))
      (node (ref "IC5") (pin "2") (pinfunction "SCL_2") (pintype "bidirectional"))
      (node (ref "SBRIO_MEZZANINE") (pin "228") (pinfunction "DIO0_228") (pintype "bidirectional"))
    )
    (net (code "34") (name "DIO1") (class "Default")
      (node (ref "C16") (pin "1") (pinfunction "1_1") (pintype "passive"))
      (node (ref "IC12") (pin "P$3") (pinfunction "3.3V_OUT_P$3") (pintype "bidirectional"))
      (node (ref "SBRIO_MEZZANINE") (pin "216") (pinfunction "DIO1_216") (pintype "bidirectional"))
    )
    (net (code "35") (name "DIO5") (class "Default")
      (node (ref "IC2") (pin "7") (pinfunction "IN3_7") (pintype "input"))
      (node (ref "SBRIO_MEZZANINE") (pin "180") (pinfunction "DIO5_180") (pintype "bidirectional"))
    )
    (net (code "36") (name "DIO6") (class "Default")
      (node (ref "IC2") (pin "5") (pinfunction "IN2_5") (pintype "input"))
      (node (ref "SBRIO_MEZZANINE") (pin "174") (pinfunction "DIO6_174") (pintype "bidirectional"))
    )
    (net (code "37") (name "DIO7") (class "Default")
      (node (ref "C20") (pin "1") (pinfunction "1_1") (pintype "passive"))
      (node (ref "IC8") (pin "P$3") (pinfunction "3.3V_OUT_P$3") (pintype "bidirectional"))
      (node (ref "SBRIO_MEZZANINE") (pin "162") (pinfunction "DIO7_162") (pintype "bidirectional"))
    )
    (net (code "38") (name "DIO8") (class "Default")
      (node (ref "IC1") (pin "9") (pinfunction "IN4_9") (pintype "input"))
      (node (ref "SBRIO_MEZZANINE") (pin "156") (pinfunction "DIO8_156") (pintype "bidirectional"))
    )
    (net (code "39") (name "DIO9") (class "Default")
      (node (ref "IC1") (pin "3") (pinfunction "IN1_3") (pintype "input"))
      (node (ref "SBRIO_MEZZANINE") (pin "144") (pinfunction "DIO9_144") (pintype "bidirectional"))
    )
    (net (code "40") (name "DIO10") (class "Default")
      (node (ref "IC3") (pin "9") (pinfunction "IN4_9") (pintype "input"))
      (node (ref "SBRIO_MEZZANINE") (pin "138") (pinfunction "DIO10_138") (pintype "bidirectional"))
    )
    (net (code "41") (name "DIO11") (class "Default")
      (node (ref "IC3") (pin "3") (pinfunction "IN1_3") (pintype "input"))
      (node (ref "SBRIO_MEZZANINE") (pin "126") (pinfunction "DIO11_126") (pintype "bidirectional"))
    )
    (net (code "42") (name "DIO16") (class "Default")
      (node (ref "IC4") (pin "7") (pinfunction "CS_7") (pintype "bidirectional"))
      (node (ref "SBRIO_MEZZANINE") (pin "231") (pinfunction "DIO16_231") (pintype "bidirectional"))
    )
    (net (code "43") (name "DIO17") (class "Default")
      (node (ref "IC4") (pin "9") (pinfunction "INT2_9") (pintype "bidirectional"))
      (node (ref "SBRIO_MEZZANINE") (pin "225") (pinfunction "DIO17_225") (pintype "bidirectional"))
    )
    (net (code "44") (name "DIO18") (class "Default")
      (node (ref "IC4") (pin "13") (pinfunction "SDA_13") (pintype "bidirectional"))
      (node (ref "IC5") (pin "3") (pinfunction "SDA/SDI_3") (pintype "bidirectional"))
      (node (ref "SBRIO_MEZZANINE") (pin "213") (pinfunction "DIO18_213") (pintype "bidirectional"))
    )
    (net (code "45") (name "DIO32") (class "Default")
      (node (ref "IC5") (pin "5") (pinfunction "CS_5") (pintype "bidirectional"))
      (node (ref "SBRIO_MEZZANINE") (pin "221") (pinfunction "DIO32_221") (pintype "bidirectional"))
    )
    (net (code "46") (name "DIO37") (class "Default")
      (node (ref "IC2") (pin "9") (pinfunction "IN4_9") (pintype "input"))
      (node (ref "SBRIO_MEZZANINE") (pin "179") (pinfunction "DIO37_179") (pintype "bidirectional"))
    )
    (net (code "47") (name "DIO38") (class "Default")
      (node (ref "IC2") (pin "3") (pinfunction "IN1_3") (pintype "input"))
      (node (ref "SBRIO_MEZZANINE") (pin "167") (pinfunction "DIO38_167") (pintype "bidirectional"))
    )
    (net (code "48") (name "DIO39") (class "Default")
      (node (ref "C17") (pin "1") (pinfunction "1_1") (pintype "passive"))
      (node (ref "IC11") (pin "P$3") (pinfunction "3.3V_OUT_P$3") (pintype "bidirectional"))
      (node (ref "SBRIO_MEZZANINE") (pin "161") (pinfunction "DIO39_161") (pintype "bidirectional"))
    )
    (net (code "49") (name "DIO40") (class "Default")
      (node (ref "IC1") (pin "7") (pinfunction "IN3_7") (pintype "input"))
      (node (ref "SBRIO_MEZZANINE") (pin "149") (pinfunction "DIO40_149") (pintype "bidirectional"))
    )
    (net (code "50") (name "DIO41") (class "Default")
      (node (ref "IC1") (pin "5") (pinfunction "IN2_5") (pintype "input"))
      (node (ref "SBRIO_MEZZANINE") (pin "143") (pinfunction "DIO41_143") (pintype "bidirectional"))
    )
    (net (code "51") (name "DIO42") (class "Default")
      (node (ref "IC3") (pin "7") (pinfunction "IN3_7") (pintype "input"))
      (node (ref "SBRIO_MEZZANINE") (pin "131") (pinfunction "DIO42_131") (pintype "bidirectional"))
    )
    (net (code "52") (name "DIO43") (class "Default")
      (node (ref "IC3") (pin "5") (pinfunction "IN2_5") (pintype "input"))
      (node (ref "SBRIO_MEZZANINE") (pin "125") (pinfunction "DIO43_125") (pintype "bidirectional"))
    )
    (net (code "53") (name "DIO44") (class "Default")
      (node (ref "R33") (pin "1") (pinfunction "1_1") (pintype "passive"))
      (node (ref "SBRIO_MEZZANINE") (pin "113") (pinfunction "DIO44_113") (pintype "bidirectional"))
    )
    (net (code "54") (name "DIO45") (class "Default")
      (node (ref "R31") (pin "1") (pinfunction "1_1") (pintype "passive"))
      (node (ref "SBRIO_MEZZANINE") (pin "107") (pinfunction "DIO45_107") (pintype "bidirectional"))
    )
    (net (code "55") (name "DIO48") (class "Default")
      (node (ref "IC4") (pin "8") (pinfunction "INT1_8") (pintype "bidirectional"))
      (node (ref "SBRIO_MEZZANINE") (pin "230") (pinfunction "DIO48_230") (pintype "bidirectional"))
    )
    (net (code "56") (name "DIO64") (class "Default")
      (node (ref "IC5") (pin "6") (pinfunction "INT2_6") (pintype "bidirectional"))
      (node (ref "SBRIO_MEZZANINE") (pin "226") (pinfunction "DIO64_226") (pintype "bidirectional"))
    )
    (net (code "57") (name "DIO65") (class "Default")
      (node (ref "IC5") (pin "7") (pinfunction "INT1_7") (pintype "bidirectional"))
      (node (ref "SBRIO_MEZZANINE") (pin "220") (pinfunction "DIO65_220") (pintype "bidirectional"))
    )
    (net (code "58") (name "DIO81") (class "Default")
      (node (ref "IC4") (pin "12") (pinfunction "SDO_12") (pintype "bidirectional"))
      (node (ref "IC5") (pin "4") (pinfunction "SDO_4") (pintype "bidirectional"))
      (node (ref "SBRIO_MEZZANINE") (pin "223") (pinfunction "DIO81_223") (pintype "bidirectional"))
    )
    (net (code "59") (name "DIO83") (class "Default")
      (node (ref "LEVEL_SHIFTER") (pin "8") (pinfunction "OE_8") (pintype "bidirectional"))
      (node (ref "SBRIO_MEZZANINE") (pin "205") (pinfunction "DIO83_205") (pintype "bidirectional"))
    )
    (net (code "60") (name "DIO85") (class "Default")
      (node (ref "LEVEL_SHIFTER") (pin "5") (pinfunction "A4_5") (pintype "bidirectional"))
      (node (ref "SBRIO_MEZZANINE") (pin "187") (pinfunction "DIO85_187") (pintype "bidirectional"))
    )
    (net (code "61") (name "DIO86") (class "Default")
      (node (ref "LEVEL_SHIFTER") (pin "4") (pinfunction "A3_4") (pintype "bidirectional"))
      (node (ref "SBRIO_MEZZANINE") (pin "181") (pinfunction "DIO86_181") (pintype "bidirectional"))
    )
    (net (code "62") (name "DIO87") (class "Default")
      (node (ref "LEVEL_SHIFTER") (pin "3") (pinfunction "A2_3") (pintype "bidirectional"))
      (node (ref "SBRIO_MEZZANINE") (pin "169") (pinfunction "DIO87_169") (pintype "bidirectional"))
    )
    (net (code "63") (name "DIO88") (class "Default")
      (node (ref "LEVEL_SHIFTER") (pin "2") (pinfunction "A1_2") (pintype "bidirectional"))
      (node (ref "SBRIO_MEZZANINE") (pin "163") (pinfunction "DIO88_163") (pintype "bidirectional"))
    )
    (net (code "64") (name "DIO89") (class "Default")
      (node (ref "SBRIO_AUX") (pin "P$12") (pinfunction "DIO18_P$12") (pintype "bidirectional"))
    )
    (net (code "65") (name "DIO90") (class "Default")
      (node (ref "SBRIO_AUX") (pin "P$10") (pinfunction "DIO19_P$10") (pintype "bidirectional"))
      (node (ref "SBRIO_MEZZANINE") (pin "145") (pinfunction "DIO90_145") (pintype "bidirectional"))
    )
    (net (code "66") (name "DIO91") (class "Default")
      (node (ref "SBRIO_AUX") (pin "P$8") (pinfunction "DIO38_P$8") (pintype "bidirectional"))
      (node (ref "SBRIO_MEZZANINE") (pin "133") (pinfunction "DIO91_133") (pintype "bidirectional"))
    )
    (net (code "67") (name "DIO92") (class "Default")
      (node (ref "SBRIO_AUX") (pin "P$5") (pinfunction "DIO15_P$5") (pintype "bidirectional"))
      (node (ref "SBRIO_MEZZANINE") (pin "127") (pinfunction "DIO92_127") (pintype "bidirectional"))
    )
    (net (code "68") (name "DIO93") (class "Default")
      (node (ref "SBRIO_AUX") (pin "P$3") (pinfunction "DIO14_P$3") (pintype "bidirectional"))
      (node (ref "SBRIO_MEZZANINE") (pin "115") (pinfunction "DIO93_115") (pintype "bidirectional"))
    )
    (net (code "69") (name "DIO94") (class "Default")
      (node (ref "C19") (pin "1") (pinfunction "1_1") (pintype "passive"))
      (node (ref "IC9") (pin "P$3") (pinfunction "3.3V_OUT_P$3") (pintype "bidirectional"))
      (node (ref "SBRIO_MEZZANINE") (pin "109") (pinfunction "DIO94_109") (pintype "bidirectional"))
    )
    (net (code "70") (name "DIO95") (class "Default")
      (node (ref "C18") (pin "1") (pinfunction "1_1") (pintype "passive"))
      (node (ref "IC10") (pin "P$3") (pinfunction "3.3V_OUT_P$3") (pintype "bidirectional"))
      (node (ref "SBRIO_MEZZANINE") (pin "97") (pinfunction "DIO95_97") (pintype "bidirectional"))
    )
    (net (code "71") (name "DIO_GND") (class "Default")
      (node (ref "C7") (pin "2") (pinfunction "2_2") (pintype "passive"))
      (node (ref "C8") (pin "2") (pinfunction "2_2") (pintype "passive"))
      (node (ref "IC4") (pin "2") (pinfunction "GND_2") (pintype "bidirectional"))
      (node (ref "IC4") (pin "4") (pinfunction "GND_4") (pintype "bidirectional"))
      (node (ref "IC4") (pin "5") (pinfunction "GND_5") (pintype "bidirectional"))
      (node (ref "SBRIO_ANALOG") (pin "P$1") (pinfunction "AI_GND_P$1") (pintype "input"))
      (node (ref "SBRIO_ANALOG") (pin "P$10") (pinfunction "AI_GND_P$10") (pintype "input"))
      (node (ref "SBRIO_ANALOG") (pin "P$13") (pinfunction "AI_GND_P$13") (pintype "input"))
      (node (ref "SBRIO_ANALOG") (pin "P$16") (pinfunction "AI_GND_P$16") (pintype "input"))
      (node (ref "SBRIO_ANALOG") (pin "P$19") (pinfunction "AI_GND_P$19") (pintype "input"))
      (node (ref "SBRIO_ANALOG") (pin "P$22") (pinfunction "AI_GND_P$22") (pintype "input"))
      (node (ref "SBRIO_ANALOG") (pin "P$25") (pinfunction "AI_GND_P$25") (pintype "input"))
      (node (ref "SBRIO_ANALOG") (pin "P$26") (pinfunction "AI_GND_P$26") (pintype "input"))
      (node (ref "SBRIO_ANALOG") (pin "P$27") (pinfunction "AO_GND_P$27") (pintype "power_in"))
      (node (ref "SBRIO_ANALOG") (pin "P$29") (pinfunction "AO_GND_P$29") (pintype "power_in"))
      (node (ref "SBRIO_ANALOG") (pin "P$31") (pinfunction "AO_GND_P$31") (pintype "power_in"))
      (node (ref "SBRIO_ANALOG") (pin "P$33") (pinfunction "AO_GND_P$33") (pintype "power_in"))
      (node (ref "SBRIO_ANALOG") (pin "P$35") (pinfunction "AO_GND_P$35") (pintype "power_in"))
      (node (ref "SBRIO_ANALOG") (pin "P$37") (pinfunction "AO_GND_P$37") (pintype "power_in"))
      (node (ref "SBRIO_ANALOG") (pin "P$39") (pinfunction "AO_GND_P$39") (pintype "power_in"))
      (node (ref "SBRIO_ANALOG") (pin "P$4") (pinfunction "AI_GND_P$4") (pintype "input"))
      (node (ref "SBRIO_ANALOG") (pin "P$41") (pinfunction "AO_GND_P$41") (pintype "power_in"))
      (node (ref "SBRIO_ANALOG") (pin "P$43") (pinfunction "DIO_GND_P$43") (pintype "power_in"))
      (node (ref "SBRIO_ANALOG") (pin "P$45") (pinfunction "DIO_GND_P$45") (pintype "power_in"))
      (node (ref "SBRIO_ANALOG") (pin "P$47") (pinfunction "DIO_GND_P$47") (pintype "power_in"))
      (node (ref "SBRIO_ANALOG") (pin "P$49") (pinfunction "DIO_GND_P$49") (pintype "power_in"))
      (node (ref "SBRIO_ANALOG") (pin "P$7") (pinfunction "AI_GND_P$7") (pintype "input"))
    )
    (net (code "72") (name "FAN_PWM_OUT") (class "Default")
      (node (ref "IC3") (pin "13") (pinfunction "OUT4_13") (pintype "output"))
      (node (ref "U$4") (pin "P6") (pinfunction "P$6_P6") (pintype "bidirectional"))
    )
    (net (code "73") (name "GND") (class "Default")
      (node (ref "C11") (pin "2") (pinfunction "2_2") (pintype "passive"))
      (node (ref "C12") (pin "2") (pinfunction "2_2") (pintype "passive"))
      (node (ref "C14") (pin "1") (pinfunction "1_1") (pintype "passive"))
      (node (ref "C16") (pin "2") (pinfunction "2_2") (pintype "passive"))
      (node (ref "C17") (pin "2") (pinfunction "2_2") (pintype "passive"))
      (node (ref "C18") (pin "2") (pinfunction "2_2") (pintype "passive"))
      (node (ref "C19") (pin "2") (pinfunction "2_2") (pintype "passive"))
      (node (ref "C20") (pin "2") (pinfunction "2_2") (pintype "passive"))
      (node (ref "C5") (pin "2") (pinfunction "2_2") (pintype "passive"))
      (node (ref "C6") (pin "2") (pinfunction "2_2") (pintype "passive"))
      (node (ref "D7") (pin "P$2") (pinfunction "A_P$2") (pintype "passive"))
      (node (ref "D8") (pin "P$2") (pinfunction "A_P$2") (pintype "passive"))
      (node (ref "IC1") (pin "2") (pinfunction "GND1/2_2") (pintype "input"))
      (node (ref "IC1") (pin "6") (pinfunction "GND3/4_6") (pintype "input"))
      (node (ref "IC10") (pin "P$2") (pinfunction "GND_P$2") (pintype "bidirectional"))
      (node (ref "IC11") (pin "P$2") (pinfunction "GND_P$2") (pintype "bidirectional"))
      (node (ref "IC12") (pin "P$2") (pinfunction "GND_P$2") (pintype "bidirectional"))
      (node (ref "IC2") (pin "2") (pinfunction "GND1/2_2") (pintype "input"))
      (node (ref "IC2") (pin "6") (pinfunction "GND3/4_6") (pintype "input"))
      (node (ref "IC3") (pin "2") (pinfunction "GND1/2_2") (pintype "input"))
      (node (ref "IC3") (pin "6") (pinfunction "GND3/4_6") (pintype "input"))
      (node (ref "IC5") (pin "10") (pinfunction "RSVDG_10") (pintype "bidirectional"))
      (node (ref "IC5") (pin "11") (pinfunction "RSDVG_11") (pintype "bidirectional"))
      (node (ref "IC5") (pin "12") (pinfunction "RSVDG_12") (pintype "bidirectional"))
      (node (ref "IC5") (pin "13") (pinfunction "GND_13") (pintype "bidirectional"))
      (node (ref "IC5") (pin "8") (pinfunction "RSVDG_8") (pintype "bidirectional"))
      (node (ref "IC5") (pin "9") (pinfunction "RSVDG_9") (pintype "bidirectional"))
      (node (ref "IC8") (pin "P$2") (pinfunction "GND_P$2") (pintype "bidirectional"))
      (node (ref "IC9") (pin "P$2") (pinfunction "GND_P$2") (pintype "bidirectional"))
      (node (ref "K1") (pin "C-") (pinfunction "C-_C-") (pintype "passive"))
      (node (ref "K2") (pin "C-") (pinfunction "C-_C-") (pintype "passive"))
      (node (ref "K3") (pin "C-") (pinfunction "C-_C-") (pintype "passive"))
      (node (ref "K4") (pin "C-") (pinfunction "C-_C-") (pintype "passive"))
      (node (ref "K6") (pin "C-") (pinfunction "C-_C-") (pintype "passive"))
      (node (ref "LATCH_U7") (pin "COIL_1") (pinfunction "C_1_COIL_1") (pintype "bidirectional"))
      (node (ref "LEVEL_SHIFTER") (pin "7") (pinfunction "GND_7") (pintype "bidirectional"))
      (node (ref "Q3") (pin "P$3") (pinfunction "E_P$3") (pintype "passive"))
      (node (ref "Q4") (pin "P$3") (pinfunction "E_P$3") (pintype "passive"))
      (node (ref "R15") (pin "2") (pinfunction "2_2") (pintype "passive"))
      (node (ref "R27") (pin "2") (pinfunction "2_2") (pintype "passive"))
      (node (ref "R28") (pin "2") (pinfunction "2_2") (pintype "passive"))
      (node (ref "R29") (pin "2") (pinfunction "2_2") (pintype "passive"))
      (node (ref "R37") (pin "1") (pinfunction "1_1") (pintype "passive"))
      (node (ref "R38") (pin "2") (pinfunction "2_2") (pintype "passive"))
      (node (ref "R39") (pin "2") (pinfunction "2_2") (pintype "passive"))
      (node (ref "R40") (pin "2") (pinfunction "2_2") (pintype "passive"))
      (node (ref "R41") (pin "2") (pinfunction "2_2") (pintype "passive"))
      (node (ref "R42") (pin "2") (pinfunction "2_2") (pintype "passive"))
      (node (ref "R43") (pin "2") (pinfunction "2_2") (pintype "passive"))
      (node (ref "R44") (pin "2") (pinfunction "2_2") (pintype "passive"))
      (node (ref "R45") (pin "2") (pinfunction "2_2") (pintype "passive"))
      (node (ref "R46") (pin "1") (pinfunction "1_1") (pintype "passive"))
      (node (ref "R47") (pin "1") (pinfunction "1_1") (pintype "passive"))
      (node (ref "R48") (pin "1") (pinfunction "1_1") (pintype "passive"))
      (node (ref "R49") (pin "1") (pinfunction "1_1") (pintype "passive"))
      (node (ref "R50") (pin "1") (pinfunction "1_1") (pintype "passive"))
      (node (ref "R51") (pin "1") (pinfunction "1_1") (pintype "passive"))
      (node (ref "R52") (pin "1") (pinfunction "1_1") (pintype "passive"))
      (node (ref "R53") (pin "1") (pinfunction "1_1") (pintype "passive"))
      (node (ref "SBRIO_AUX") (pin "P$11") (pinfunction "GND_P$11") (pintype "bidirectional"))
      (node (ref "SBRIO_AUX") (pin "P$13") (pinfunction "GND_P$13") (pintype "bidirectional"))
      (node (ref "SBRIO_AUX") (pin "P$15") (pinfunction "GND_P$15") (pintype "bidirectional"))
      (node (ref "SBRIO_AUX") (pin "P$17") (pinfunction "GND_P$17") (pintype "bidirectional"))
      (node (ref "SBRIO_AUX") (pin "P$18") (pinfunction "GND_P$18") (pintype "bidirectional"))
      (node (ref "SBRIO_AUX") (pin "P$19") (pinfunction "GND_P$19") (pintype "bidirectional"))
      (node (ref "SBRIO_AUX") (pin "P$20") (pinfunction "GND_P$20") (pintype "bidirectional"))
      (node (ref "SBRIO_AUX") (pin "P$21") (pinfunction "GND_P$21") (pintype "bidirectional"))
      (node (ref "SBRIO_AUX") (pin "P$22") (pinfunction "GND_P$22") (pintype "bidirectional"))
      (node (ref "SBRIO_AUX") (pin "P$23") (pinfunction "GND_P$23") (pintype "bidirectional"))
      (node (ref "SBRIO_AUX") (pin "P$24") (pinfunction "GND_P$24") (pintype "bidirectional"))
      (node (ref "SBRIO_AUX") (pin "P$25") (pinfunction "GND_P$25") (pintype "bidirectional"))
      (node (ref "SBRIO_AUX") (pin "P$26") (pinfunction "GND_P$26") (pintype "bidirectional"))
      (node (ref "SBRIO_AUX") (pin "P$27") (pinfunction "GND_P$27") (pintype "bidirectional"))
      (node (ref "SBRIO_AUX") (pin "P$28") (pinfunction "GND_P$28") (pintype "bidirectional"))
      (node (ref "SBRIO_AUX") (pin "P$29") (pinfunction "GND_P$29") (pintype "bidirectional"))
      (node (ref "SBRIO_AUX") (pin "P$30") (pinfunction "GND_P$30") (pintype "bidirectional"))
      (node (ref "SBRIO_AUX") (pin "P$31") (pinfunction "GND_P$31") (pintype "bidirectional"))
      (node (ref "SBRIO_AUX") (pin "P$32") (pinfunction "GND_P$32") (pintype "bidirectional"))
      (node (ref "SBRIO_AUX") (pin "P$34") (pinfunction "GND_P$34") (pintype "bidirectional"))
      (node (ref "SBRIO_AUX") (pin "P$36") (pinfunction "GND_P$36") (pintype "bidirectional"))
      (node (ref "SBRIO_AUX") (pin "P$38") (pinfunction "GND_P$38") (pintype "bidirectional"))
      (node (ref "SBRIO_AUX") (pin "P$40") (pinfunction "GND_P$40") (pintype "bidirectional"))
      (node (ref "SBRIO_AUX") (pin "P$42") (pinfunction "GND_P$42") (pintype "bidirectional"))
      (node (ref "SBRIO_AUX") (pin "P$44") (pinfunction "GND_P$44") (pintype "bidirectional"))
      (node (ref "SBRIO_AUX") (pin "P$46") (pinfunction "GND_P$46") (pintype "bidirectional"))
      (node (ref "SBRIO_AUX") (pin "P$48") (pinfunction "GND_P$48") (pintype "bidirectional"))
      (node (ref "SBRIO_AUX") (pin "P$50") (pinfunction "GND_P$50") (pintype "bidirectional"))
      (node (ref "SBRIO_AUX") (pin "P$7") (pinfunction "GND_P$7") (pintype "bidirectional"))
      (node (ref "SBRIO_AUX") (pin "P$9") (pinfunction "GND_P$9") (pintype "bidirectional"))
      (node (ref "SBRIO_MEZZANINE") (pin "237") (pinfunction "GND_237") (pintype "power_in"))
      (node (ref "U$1") (pin "P$3") (pinfunction "GND_P$3") (pintype "bidirectional"))
      (node (ref "U$1") (pin "P$6") (pinfunction "GND_P$6") (pintype "bidirectional"))
      (node (ref "U$2") (pin "2") (pinfunction "2_2") (pintype "passive"))
      (node (ref "U$3") (pin "2") (pinfunction "GND_2") (pintype "bidirectional"))
      (node (ref "U$3") (pin "4") (pinfunction "GND_4") (pintype "bidirectional"))
      (node (ref "U$4") (pin "P3") (pinfunction "P$3_P3") (pintype "bidirectional"))
      (node (ref "U$4") (pin "P7") (pinfunction "P$7_P7") (pintype "bidirectional"))
      (node (ref "U$6") (pin "A1") (pinfunction "A1_A1") (pintype "bidirectional"))
      (node (ref "U$6") (pin "A11") (pinfunction "A11_A11") (pintype "bidirectional"))
      (node (ref "U$6") (pin "A14") (pinfunction "A14_A14") (pintype "bidirectional"))
      (node (ref "U$6") (pin "A16") (pinfunction "A16_A16") (pintype "bidirectional"))
      (node (ref "U$6") (pin "A17") (pinfunction "A17_A17") (pintype "bidirectional"))
      (node (ref "U$6") (pin "A18") (pinfunction "A18_A18") (pintype "bidirectional"))
      (node (ref "U$6") (pin "A19") (pinfunction "A19_A19") (pintype "bidirectional"))
      (node (ref "U$6") (pin "A20") (pinfunction "A20_A20") (pintype "bidirectional"))
      (node (ref "U$6") (pin "A32") (pinfunction "A32_A32") (pintype "bidirectional"))
      (node (ref "U$6") (pin "B12") (pinfunction "B12_B12") (pintype "bidirectional"))
      (node (ref "U$6") (pin "B13") (pinfunction "B13_B13") (pintype "bidirectional"))
      (node (ref "U$6") (pin "B15") (pinfunction "B15_B15") (pintype "bidirectional"))
      (node (ref "U$6") (pin "B16") (pinfunction "B16_B16") (pintype "bidirectional"))
      (node (ref "U$6") (pin "B17") (pinfunction "B17_B17") (pintype "bidirectional"))
      (node (ref "U$6") (pin "B18") (pinfunction "B18_B18") (pintype "bidirectional"))
      (node (ref "U$6") (pin "B19") (pinfunction "B19_B19") (pintype "bidirectional"))
      (node (ref "U$6") (pin "B22") (pinfunction "B22_B22") (pintype "bidirectional"))
      (node (ref "U$6") (pin "B23") (pinfunction "B23_B23") (pintype "bidirectional"))
      (node (ref "U$7") (pin "2") (pinfunction "2_2") (pintype "passive"))
      (node (ref "U$8") (pin "V1") (pinfunction "V1_V1") (pintype "bidirectional"))
      (node (ref "U$9") (pin "P$7") (pinfunction "P$7_P$7") (pintype "bidirectional"))
      (node (ref "U1") (pin "2") (pinfunction "S_2") (pintype "input"))
    )
    (net (code "74") (name "HIGH_CURRENT_IN") (class "Default")
      (node (ref "R2") (pin "2") (pinfunction "2_2") (pintype "passive"))
      (node (ref "R39") (pin "1") (pinfunction "1_1") (pintype "passive"))
      (node (ref "SBRIO_ANALOG") (pin "P$8") (pinfunction "AI2_P$8") (pintype "input"))
      (node (ref "U$6") (pin "B1") (pinfunction "B1_B1") (pintype "bidirectional"))
    )
    (net (code "75") (name "IMD_OK+") (class "Default")
      (node (ref "IC10") (pin "P$1") (pinfunction "3~{16V_IN}_P$1") (pintype "bidirectional"))
      (node (ref "K6") (pin "C+") (pinfunction "C+_C+") (pintype "passive"))
      (node (ref "R27") (pin "1") (pinfunction "1_1") (pintype "passive"))
      (node (ref "U$6") (pin "B3") (pinfunction "B3_B3") (pintype "bidirectional"))
    )
    (net (code "76") (name "INTER_OK+") (class "Default")
      (node (ref "K1") (pin "C+") (pinfunction "C+_C+") (pintype "passive"))
      (node (ref "U$6") (pin "B25") (pinfunction "B25_B25") (pintype "bidirectional"))
    )
    (net (code "77") (name "LATCH_LED+") (class "Default")
      (node (ref "LATCH_U7") (pin "NC_2") (pinfunction "NC_2_NC_2") (pintype "bidirectional"))
      (node (ref "U$9") (pin "P$8") (pinfunction "P$8_P$8") (pintype "bidirectional"))
    )
    (net (code "78") (name "LATCH_SW_IN") (class "Default")
      (node (ref "D7") (pin "P$1") (pinfunction "C_P$1") (pintype "passive"))
      (node (ref "LATCH_U7") (pin "COIL_2") (pinfunction "C_2_COIL_2") (pintype "bidirectional"))
      (node (ref "LATCH_U7") (pin "NO_2") (pinfunction "NO_2_NO_2") (pintype "bidirectional"))
      (node (ref "U$9") (pin "P$6") (pinfunction "P$6_P$6") (pintype "bidirectional"))
    )
    (net (code "79") (name "LATCH_SW_OUT") (class "Default")
      (node (ref "K6") (pin "S2") (pinfunction "SW_2_S2") (pintype "passive"))
      (node (ref "LATCH_U7") (pin "CENTER_2") (pinfunction "IN_2_CENTER_2") (pintype "bidirectional"))
      (node (ref "U$9") (pin "P$5") (pinfunction "P$5_P$5") (pintype "bidirectional"))
    )
    (net (code "80") (name "LOW_CURRENT_IN") (class "Default")
      (node (ref "R53") (pin "2") (pinfunction "2_2") (pintype "passive"))
      (node (ref "SBRIO_ANALOG") (pin "P$6") (pinfunction "AI1_P$6") (pintype "input"))
      (node (ref "U$6") (pin "B2") (pinfunction "B2_B2") (pintype "bidirectional"))
    )
    (net (code "81") (name "Net-(C13-Pad1)") (class "Default")
      (node (ref "C13") (pin "1") (pinfunction "1_1") (pintype "passive"))
      (node (ref "R38") (pin "1") (pinfunction "1_1") (pintype "passive"))
    )
    (net (code "82") (name "Net-(D6-A)") (class "Default")
      (node (ref "D6") (pin "P$2") (pinfunction "A_P$2") (pintype "passive"))
      (node (ref "R37") (pin "2") (pinfunction "2_2") (pintype "passive"))
      (node (ref "SBRIO_ANALOG") (pin "P$2") (pinfunction "AI0_P$2") (pintype "input"))
    )
    (net (code "83") (name "Net-(F2-Pad2)") (class "Default")
      (node (ref "F2") (pin "2") (pinfunction "2_2") (pintype "passive"))
      (node (ref "K3") (pin "C+") (pinfunction "C+_C+") (pintype "passive"))
    )
    (net (code "84") (name "Net-(F3-1-Pad2)") (class "Default")
      (node (ref "F3") (pin "1") (pinfunction "1_1") (pintype "bidirectional"))
      (node (ref "F3") (pin "2") (pinfunction "1_2") (pintype "bidirectional"))
      (node (ref "U$8") (pin "A") (pinfunction "A_A") (pintype "bidirectional"))
    )
    (net (code "85") (name "Net-(F5-Pad2)") (class "Default")
      (node (ref "F5") (pin "2") (pinfunction "2_2") (pintype "passive"))
      (node (ref "U$6") (pin "A29") (pinfunction "A29_A29") (pintype "bidirectional"))
    )
    (net (code "86") (name "Net-(F7-Pad2)") (class "Default")
      (node (ref "F7") (pin "2") (pinfunction "2_2") (pintype "passive"))
      (node (ref "U$6") (pin "A28") (pinfunction "A28_A28") (pintype "bidirectional"))
    )
    (net (code "87") (name "Net-(F8-Pad2)") (class "Default")
      (node (ref "F8") (pin "2") (pinfunction "2_2") (pintype "passive"))
      (node (ref "U$6") (pin "A27") (pinfunction "A27_A27") (pintype "bidirectional"))
    )
    (net (code "88") (name "Net-(F9-Pad2)") (class "Default")
      (node (ref "F9") (pin "2") (pinfunction "2_2") (pintype "passive"))
      (node (ref "U$6") (pin "A26") (pinfunction "A26_A26") (pintype "bidirectional"))
    )
    (net (code "89") (name "Net-(F14-Pad2)") (class "Default")
      (node (ref "F14") (pin "2") (pinfunction "2_2") (pintype "passive"))
      (node (ref "K2") (pin "C+") (pinfunction "C+_C+") (pintype "passive"))
    )
    (net (code "90") (name "Net-(IC5-PLL)") (class "Default")
      (node (ref "C13") (pin "2") (pinfunction "2_2") (pintype "passive"))
      (node (ref "C14") (pin "2") (pinfunction "2_2") (pintype "passive"))
      (node (ref "IC5") (pin "14") (pinfunction "PLL_14") (pintype "bidirectional"))
    )
    (net (code "91") (name "Net-(IC9-3~{16V_IN})") (class "Default")
      (node (ref "IC9") (pin "P$1") (pinfunction "3~{16V_IN}_P$1") (pintype "bidirectional"))
      (node (ref "R6") (pin "2") (pinfunction "2_2") (pintype "passive"))
      (node (ref "U1") (pin "3") (pinfunction "D_3") (pintype "output"))
    )
    (net (code "92") (name "Net-(K1-SW_1)") (class "Default")
      (node (ref "K1") (pin "S1") (pinfunction "SW_1_S1") (pintype "passive"))
      (node (ref "K2") (pin "S2") (pinfunction "SW_2_S2") (pintype "passive"))
    )
    (net (code "93") (name "Net-(K2-SW_1)") (class "Default")
      (node (ref "K2") (pin "S1") (pinfunction "SW_1_S1") (pintype "passive"))
      (node (ref "K3") (pin "S2") (pinfunction "SW_2_S2") (pintype "passive"))
    )
    (net (code "94") (name "Net-(K4-SW_2)") (class "Default")
      (node (ref "K4") (pin "S2") (pinfunction "SW_2_S2") (pintype "passive"))
      (node (ref "K5") (pin "S1") (pinfunction "SW_1_S1") (pintype "passive"))
    )
    (net (code "95") (name "Net-(K5-SW_2)") (class "Default")
      (node (ref "K5") (pin "S2") (pinfunction "SW_2_S2") (pintype "passive"))
      (node (ref "K6") (pin "S1") (pinfunction "SW_1_S1") (pintype "passive"))
    )
    (net (code "96") (name "Net-(Q1-B)") (class "Default")
      (node (ref "Q1") (pin "P$2") (pinfunction "B_P$2") (pintype "passive"))
      (node (ref "R34") (pin "2") (pinfunction "2_2") (pintype "passive"))
    )
    (net (code "97") (name "Net-(Q1-C)") (class "Default")
      (node (ref "F17") (pin "2") (pinfunction "2_2") (pintype "passive"))
      (node (ref "Q1") (pin "P$1") (pinfunction "C_P$1") (pintype "passive"))
    )
    (net (code "98") (name "Net-(Q2-B)") (class "Default")
      (node (ref "Q2") (pin "P$2") (pinfunction "B_P$2") (pintype "passive"))
      (node (ref "R32") (pin "2") (pinfunction "2_2") (pintype "passive"))
    )
    (net (code "99") (name "Net-(Q2-C)") (class "Default")
      (node (ref "F18") (pin "2") (pinfunction "2_2") (pintype "passive"))
      (node (ref "Q2") (pin "P$1") (pinfunction "C_P$1") (pintype "passive"))
    )
    (net (code "100") (name "Net-(Q3-B)") (class "Default")
      (node (ref "Q3") (pin "P$2") (pinfunction "B_P$2") (pintype "passive"))
      (node (ref "R33") (pin "2") (pinfunction "2_2") (pintype "passive"))
    )
    (net (code "101") (name "Net-(Q3-C)") (class "Default")
      (node (ref "Q3") (pin "P$1") (pinfunction "C_P$1") (pintype "passive"))
      (node (ref "R34") (pin "1") (pinfunction "1_1") (pintype "passive"))
    )
    (net (code "102") (name "Net-(Q4-B)") (class "Default")
      (node (ref "Q4") (pin "P$2") (pinfunction "B_P$2") (pintype "passive"))
      (node (ref "R31") (pin "2") (pinfunction "2_2") (pintype "passive"))
    )
    (net (code "103") (name "Net-(Q4-C)") (class "Default")
      (node (ref "Q4") (pin "P$1") (pinfunction "C_P$1") (pintype "passive"))
      (node (ref "R32") (pin "1") (pinfunction "1_1") (pintype "passive"))
    )
    (net (code "104") (name "Net-(U$10-2)") (class "Default")
      (node (ref "R1") (pin "1") (pinfunction "1_1") (pintype "passive"))
      (node (ref "U$10") (pin "P2") (pinfunction "2_P2") (pintype "bidirectional"))
    )
    (net (code "105") (name "Net-(U$10-3)") (class "Default")
      (node (ref "R2") (pin "1") (pinfunction "1_1") (pintype "passive"))
      (node (ref "U$10") (pin "P3") (pinfunction "3_P3") (pintype "bidirectional"))
    )
    (net (code "106") (name "Net-(U$10-4)") (class "Default")
      (node (ref "R3") (pin "1") (pinfunction "1_1") (pintype "passive"))
      (node (ref "U$10") (pin "P4") (pinfunction "4_P4") (pintype "bidirectional"))
    )
    (net (code "107") (name "Net-(U$10-5)") (class "Default")
      (node (ref "R4") (pin "1") (pinfunction "1_1") (pintype "passive"))
      (node (ref "U$10") (pin "P5") (pinfunction "5_P5") (pintype "bidirectional"))
    )
    (net (code "108") (name "Net-(U$10-6)") (class "Default")
      (node (ref "R5") (pin "1") (pinfunction "1_1") (pintype "passive"))
      (node (ref "U$10") (pin "P6") (pinfunction "6_P6") (pintype "bidirectional"))
    )
    (net (code "109") (name "PO3") (class "Default")
      (node (ref "IC1") (pin "14") (pinfunction "OUT3_14") (pintype "output"))
      (node (ref "K5") (pin "C+") (pinfunction "C+_C+") (pintype "passive"))
      (node (ref "U$6") (pin "A13") (pinfunction "A13_A13") (pintype "bidirectional"))
    )
    (net (code "110") (name "POSITIVE_AIR_ENABLE") (class "Default")
      (node (ref "IC3") (pin "14") (pinfunction "OUT3_14") (pintype "output"))
      (node (ref "U$6") (pin "B8") (pinfunction "B8_B8") (pintype "bidirectional"))
    )
    (net (code "111") (name "PRECHARGE_DONE+") (class "Default")
      (node (ref "IC1") (pin "13") (pinfunction "OUT4_13") (pintype "output"))
      (node (ref "U$6") (pin "B24") (pinfunction "B24_B24") (pintype "bidirectional"))
    )
    (net (code "112") (name "SBRIO_OK+_1") (class "Default")
      (node (ref "F2") (pin "1") (pinfunction "1_1") (pintype "passive"))
      (node (ref "IC2") (pin "14") (pinfunction "OUT3_14") (pintype "output"))
    )
    (net (code "113") (name "SBRIO_OK+_2") (class "Default")
      (node (ref "F14") (pin "1") (pinfunction "1_1") (pintype "passive"))
      (node (ref "IC2") (pin "17") (pinfunction "OUT2_17") (pintype "output"))
    )
    (net (code "114") (name "SHUTDOWN_3") (class "Default")
      (node (ref "IC2") (pin "13") (pinfunction "OUT4_13") (pintype "output"))
    )
    (net (code "115") (name "SHUTDOWN_OK+") (class "Default")
      (node (ref "K1") (pin "S2") (pinfunction "SW_2_S2") (pintype "passive"))
      (node (ref "LATCH_U7") (pin "NO_1") (pinfunction "NO_1_NO_1") (pintype "bidirectional"))
    )
    (net (code "116") (name "SIGNAL_GND") (class "Default")
      (node (ref "U$10") (pin "P1") (pinfunction "1_P1") (pintype "bidirectional"))
      (node (ref "U$4") (pin "P2") (pinfunction "P$2_P2") (pintype "bidirectional"))
      (node (ref "U$6") (pin "B5") (pinfunction "B5_B5") (pintype "bidirectional"))
    )
    (net (code "117") (name "STEERING_POS") (class "Default")
      (node (ref "R45") (pin "1") (pinfunction "1_1") (pintype "passive"))
      (node (ref "SBRIO_ANALOG") (pin "P$21") (pinfunction "AI14_P$21") (pintype "input"))
      (node (ref "SBRIO_AUX") (pin "P$39") (pinfunction "AI14_P$39") (pintype "bidirectional"))
      (node (ref "U$6") (pin "A31") (pinfunction "A31_A31") (pintype "bidirectional"))
    )
    (net (code "118") (name "THROTTLE_IN_1") (class "Default")
      (node (ref "R51") (pin "2") (pinfunction "2_2") (pintype "passive"))
      (node (ref "SBRIO_ANALOG") (pin "P$18") (pinfunction "AI5_P$18") (pintype "input"))
      (node (ref "U$6") (pin "A8") (pinfunction "A8_A8") (pintype "bidirectional"))
    )
    (net (code "119") (name "THROTTLE_IN_2") (class "Default")
      (node (ref "R41") (pin "1") (pinfunction "1_1") (pintype "passive"))
      (node (ref "SBRIO_ANALOG") (pin "P$20") (pinfunction "AI6_P$20") (pintype "input"))
      (node (ref "U$6") (pin "A21") (pinfunction "A21_A21") (pintype "bidirectional"))
    )
    (net (code "120") (name "THROTTLE_OK_OUT") (class "Default")
      (node (ref "IC2") (pin "18") (pinfunction "OUT1_18") (pintype "output"))
      (node (ref "U$6") (pin "B14") (pinfunction "B14_B14") (pintype "bidirectional"))
    )
    (net (code "121") (name "TSMS_IN+") (class "Default")
      (node (ref "IC11") (pin "P$1") (pinfunction "3~{16V_IN}_P$1") (pintype "bidirectional"))
      (node (ref "R28") (pin "1") (pinfunction "1_1") (pintype "passive"))
      (node (ref "U$6") (pin "A15") (pinfunction "A15_A15") (pintype "bidirectional"))
      (node (ref "U$6") (pin "B10") (pinfunction "B10_B10") (pintype "bidirectional"))
    )
    (net (code "122") (name "TSMS_OUT+") (class "Default")
      (node (ref "IC8") (pin "P$1") (pinfunction "3~{16V_IN}_P$1") (pintype "bidirectional"))
      (node (ref "R15") (pin "1") (pinfunction "1_1") (pintype "passive"))
      (node (ref "U$6") (pin "A3") (pinfunction "A3_A3") (pintype "bidirectional"))
      (node (ref "U$8") (pin "CENTER") (pinfunction "C_CENTER") (pintype "bidirectional"))
    )
    (net (code "123") (name "TSMS_OUT_CTRL+") (class "Default")
      (node (ref "D8") (pin "P$1") (pinfunction "C_P$1") (pintype "passive"))
      (node (ref "LATCH_U7") (pin "CENTER_1") (pinfunction "IN_1_CENTER_1") (pintype "bidirectional"))
      (node (ref "U$8") (pin "V2") (pinfunction "V2_V2") (pintype "bidirectional"))
    )
    (net (code "124") (name "WS1") (class "Default")
      (node (ref "LEVEL_SHIFTER") (pin "13") (pinfunction "B1_13") (pintype "bidirectional"))
      (node (ref "U$6") (pin "A22") (pinfunction "A22_A22") (pintype "bidirectional"))
    )
    (net (code "125") (name "WS2") (class "Default")
      (node (ref "LEVEL_SHIFTER") (pin "12") (pinfunction "B2_12") (pintype "bidirectional"))
      (node (ref "U$6") (pin "A23") (pinfunction "A23_A23") (pintype "bidirectional"))
    )
    (net (code "126") (name "WS3") (class "Default")
      (node (ref "LEVEL_SHIFTER") (pin "11") (pinfunction "B3_11") (pintype "bidirectional"))
      (node (ref "U$6") (pin "A24") (pinfunction "A24_A24") (pintype "bidirectional"))
    )
    (net (code "127") (name "WS4") (class "Default")
      (node (ref "LEVEL_SHIFTER") (pin "10") (pinfunction "B4_10") (pintype "bidirectional"))
      (node (ref "U$6") (pin "A25") (pinfunction "A25_A25") (pintype "bidirectional"))
    )
    (net (code "128") (name "unconnected-(IC1A-ST1{slash}2-Pad4)") (class "Default")
      (node (ref "IC1") (pin "4") (pinfunction "ST1/2_4") (pintype "input"))
    )
    (net (code "129") (name "unconnected-(IC1A-ST3{slash}4-Pad8)") (class "Default")
      (node (ref "IC1") (pin "8") (pinfunction "ST3/4_8") (pintype "input"))
    )
    (net (code "130") (name "unconnected-(IC2A-ST1{slash}2-Pad4)") (class "Default")
      (node (ref "IC2") (pin "4") (pinfunction "ST1/2_4") (pintype "input"))
    )
    (net (code "131") (name "unconnected-(IC2A-ST3{slash}4-Pad8)") (class "Default")
      (node (ref "IC2") (pin "8") (pinfunction "ST3/4_8") (pintype "input"))
    )
    (net (code "132") (name "unconnected-(IC3A-ST1{slash}2-Pad4)") (class "Default")
      (node (ref "IC3") (pin "4") (pinfunction "ST1/2_4") (pintype "input"))
    )
    (net (code "133") (name "unconnected-(IC3A-ST3{slash}4-Pad8)") (class "Default")
      (node (ref "IC3") (pin "8") (pinfunction "ST3/4_8") (pintype "input"))
    )
    (net (code "134") (name "unconnected-(IC4-NC-Pad3)") (class "Default")
      (node (ref "IC4") (pin "3") (pinfunction "NC_3") (pintype "bidirectional"))
    )
    (net (code "135") (name "unconnected-(IC4-NC-Pad10)") (class "Default")
      (node (ref "IC4") (pin "10") (pinfunction "NC_10") (pintype "bidirectional"))
    )
    (net (code "136") (name "unconnected-(IC4-NC-Pad11)") (class "Default")
      (node (ref "IC4") (pin "11") (pinfunction "NC_11") (pintype "bidirectional"))
    )
    (net (code "137") (name "unconnected-(LATCH_U7-PadNC_1)") (class "Default")
      (node (ref "LATCH_U7") (pin "NC_1") (pinfunction "NC_1_NC_1") (pintype "bidirectional"))
    )
    (net (code "138") (name "unconnected-(SBRIO_ANALOG-DIO_0-PadP$44)") (class "Default")
      (node (ref "SBRIO_ANALOG") (pin "P$44") (pinfunction "DIO_0_P$44") (pintype "bidirectional"))
    )
    (net (code "139") (name "unconnected-(SBRIO_ANALOG-DIO_1-PadP$46)") (class "Default")
      (node (ref "SBRIO_ANALOG") (pin "P$46") (pinfunction "DIO_1_P$46") (pintype "bidirectional"))
    )
    (net (code "140") (name "unconnected-(SBRIO_ANALOG-DIO_2-PadP$48)") (class "Default")
      (node (ref "SBRIO_ANALOG") (pin "P$48") (pinfunction "DIO_2_P$48") (pintype "bidirectional"))
    )
    (net (code "141") (name "unconnected-(SBRIO_ANALOG-DIO_3-PadP$50)") (class "Default")
      (node (ref "SBRIO_ANALOG") (pin "P$50") (pinfunction "DIO_3_P$50") (pintype "bidirectional"))
    )
    (net (code "142") (name "unconnected-(SBRIO_AUX-DIO16-PadP$16)") (class "Default")
      (node (ref "SBRIO_AUX") (pin "P$16") (pinfunction "DIO16_P$16") (pintype "bidirectional"))
    )
    (net (code "143") (name "unconnected-(SBRIO_AUX-DIO17-PadP$14)") (class "Default")
      (node (ref "SBRIO_AUX") (pin "P$14") (pinfunction "DIO17_P$14") (pintype "bidirectional"))
    )
    (net (code "144") (name "unconnected-(SBRIO_AUX-DIO39-PadP$6)") (class "Default")
      (node (ref "SBRIO_AUX") (pin "P$6") (pinfunction "DIO39_P$6") (pintype "bidirectional"))
    )
    (net (code "145") (name "unconnected-(SBRIO_AUX-E-STOP-PadP$4)") (class "Default")
      (node (ref "SBRIO_AUX") (pin "P$4") (pinfunction "E-STOP_P$4") (pintype "bidirectional"))
    )
    (net (code "146") (name "unconnected-(SBRIO_AUX-LATCH-PadP$2)") (class "Default")
      (node (ref "SBRIO_AUX") (pin "P$2") (pinfunction "LATCH_P$2") (pintype "bidirectional"))
    )
    (net (code "147") (name "unconnected-(SBRIO_AUX-POS_AIR-PadP$1)") (class "Default")
      (node (ref "SBRIO_AUX") (pin "P$1") (pinfunction "POS_AIR_P$1") (pintype "bidirectional"))
    )
    (net (code "148") (name "unconnected-(SBRIO_MEZZANINE-DIO2-Pad210)") (class "Default")
      (node (ref "SBRIO_MEZZANINE") (pin "210") (pinfunction "DIO2_210") (pintype "bidirectional"))
    )
    (net (code "149") (name "unconnected-(SBRIO_MEZZANINE-DIO3-Pad198)") (class "Default")
      (node (ref "SBRIO_MEZZANINE") (pin "198") (pinfunction "DIO3_198") (pintype "bidirectional"))
    )
    (net (code "150") (name "unconnected-(SBRIO_MEZZANINE-DIO4-Pad192)") (class "Default")
      (node (ref "SBRIO_MEZZANINE") (pin "192") (pinfunction "DIO4_192") (pintype "bidirectional"))
    )
    (net (code "151") (name "unconnected-(SBRIO_MEZZANINE-DIO12-Pad120)") (class "Default")
      (node (ref "SBRIO_MEZZANINE") (pin "120") (pinfunction "DIO12_120") (pintype "bidirectional"))
    )
    (net (code "152") (name "unconnected-(SBRIO_MEZZANINE-DIO13-Pad108)") (class "Default")
      (node (ref "SBRIO_MEZZANINE") (pin "108") (pinfunction "DIO13_108") (pintype "bidirectional"))
    )
    (net (code "153") (name "unconnected-(SBRIO_MEZZANINE-DIO14-Pad102)") (class "Default")
      (node (ref "SBRIO_MEZZANINE") (pin "102") (pinfunction "DIO14_102") (pintype "bidirectional"))
    )
    (net (code "154") (name "unconnected-(SBRIO_MEZZANINE-DIO15-Pad90)") (class "Default")
      (node (ref "SBRIO_MEZZANINE") (pin "90") (pinfunction "DIO15_90") (pintype "bidirectional"))
    )
    (net (code "155") (name "unconnected-(SBRIO_MEZZANINE-DIO19-Pad207)") (class "Default")
      (node (ref "SBRIO_MEZZANINE") (pin "207") (pinfunction "DIO19_207") (pintype "bidirectional"))
    )
    (net (code "156") (name "unconnected-(SBRIO_MEZZANINE-DIO20-Pad195)") (class "Default")
      (node (ref "SBRIO_MEZZANINE") (pin "195") (pinfunction "DIO20_195") (pintype "bidirectional"))
    )
    (net (code "157") (name "unconnected-(SBRIO_MEZZANINE-DIO21-Pad189)") (class "Default")
      (node (ref "SBRIO_MEZZANINE") (pin "189") (pinfunction "DIO21_189") (pintype "bidirectional"))
    )
    (net (code "158") (name "unconnected-(SBRIO_MEZZANINE-DIO22-Pad177)") (class "Default")
      (node (ref "SBRIO_MEZZANINE") (pin "177") (pinfunction "DIO22_177") (pintype "bidirectional"))
    )
    (net (code "159") (name "unconnected-(SBRIO_MEZZANINE-DIO23-Pad171)") (class "Default")
      (node (ref "SBRIO_MEZZANINE") (pin "171") (pinfunction "DIO23_171") (pintype "bidirectional"))
    )
    (net (code "160") (name "unconnected-(SBRIO_MEZZANINE-DIO24-Pad159)") (class "Default")
      (node (ref "SBRIO_MEZZANINE") (pin "159") (pinfunction "DIO24_159") (pintype "bidirectional"))
    )
    (net (code "161") (name "unconnected-(SBRIO_MEZZANINE-DIO25-Pad153)") (class "Default")
      (node (ref "SBRIO_MEZZANINE") (pin "153") (pinfunction "DIO25_153") (pintype "bidirectional"))
    )
    (net (code "162") (name "unconnected-(SBRIO_MEZZANINE-DIO26-Pad141)") (class "Default")
      (node (ref "SBRIO_MEZZANINE") (pin "141") (pinfunction "DIO26_141") (pintype "bidirectional"))
    )
    (net (code "163") (name "unconnected-(SBRIO_MEZZANINE-DIO27-Pad135)") (class "Default")
      (node (ref "SBRIO_MEZZANINE") (pin "135") (pinfunction "DIO27_135") (pintype "bidirectional"))
    )
    (net (code "164") (name "unconnected-(SBRIO_MEZZANINE-DIO28-Pad123)") (class "Default")
      (node (ref "SBRIO_MEZZANINE") (pin "123") (pinfunction "DIO28_123") (pintype "bidirectional"))
    )
    (net (code "165") (name "unconnected-(SBRIO_MEZZANINE-DIO29-Pad117)") (class "Default")
      (node (ref "SBRIO_MEZZANINE") (pin "117") (pinfunction "DIO29_117") (pintype "bidirectional"))
    )
    (net (code "166") (name "unconnected-(SBRIO_MEZZANINE-DIO30-Pad105)") (class "Default")
      (node (ref "SBRIO_MEZZANINE") (pin "105") (pinfunction "DIO30_105") (pintype "bidirectional"))
    )
    (net (code "167") (name "unconnected-(SBRIO_MEZZANINE-DIO31-Pad99)") (class "Default")
      (node (ref "SBRIO_MEZZANINE") (pin "99") (pinfunction "DIO31_99") (pintype "bidirectional"))
    )
    (net (code "168") (name "unconnected-(SBRIO_MEZZANINE-DIO33-Pad215)") (class "Default")
      (node (ref "SBRIO_MEZZANINE") (pin "215") (pinfunction "DIO33_215") (pintype "bidirectional"))
    )
    (net (code "169") (name "unconnected-(SBRIO_MEZZANINE-DIO34-Pad203)") (class "Default")
      (node (ref "SBRIO_MEZZANINE") (pin "203") (pinfunction "DIO34_203") (pintype "bidirectional"))
    )
    (net (code "170") (name "unconnected-(SBRIO_MEZZANINE-DIO35-Pad197)") (class "Default")
      (node (ref "SBRIO_MEZZANINE") (pin "197") (pinfunction "DIO35_197") (pintype "bidirectional"))
    )
    (net (code "171") (name "unconnected-(SBRIO_MEZZANINE-DIO36-Pad185)") (class "Default")
      (node (ref "SBRIO_MEZZANINE") (pin "185") (pinfunction "DIO36_185") (pintype "bidirectional"))
    )
    (net (code "172") (name "unconnected-(SBRIO_MEZZANINE-DIO46-Pad95)") (class "Default")
      (node (ref "SBRIO_MEZZANINE") (pin "95") (pinfunction "DIO46_95") (pintype "bidirectional"))
    )
    (net (code "173") (name "unconnected-(SBRIO_MEZZANINE-DIO47-Pad89)") (class "Default")
      (node (ref "SBRIO_MEZZANINE") (pin "89") (pinfunction "DIO47_89") (pintype "bidirectional"))
    )
    (net (code "174") (name "unconnected-(SBRIO_MEZZANINE-DIO49-Pad218)") (class "Default")
      (node (ref "SBRIO_MEZZANINE") (pin "218") (pinfunction "DIO49_218") (pintype "bidirectional"))
    )
    (net (code "175") (name "unconnected-(SBRIO_MEZZANINE-DIO50-Pad212)") (class "Default")
      (node (ref "SBRIO_MEZZANINE") (pin "212") (pinfunction "DIO50_212") (pintype "bidirectional"))
    )
    (net (code "176") (name "unconnected-(SBRIO_MEZZANINE-DIO51-Pad200)") (class "Default")
      (node (ref "SBRIO_MEZZANINE") (pin "200") (pinfunction "DIO51_200") (pintype "bidirectional"))
    )
    (net (code "177") (name "unconnected-(SBRIO_MEZZANINE-DIO52-Pad194)") (class "Default")
      (node (ref "SBRIO_MEZZANINE") (pin "194") (pinfunction "DIO52_194") (pintype "bidirectional"))
    )
    (net (code "178") (name "unconnected-(SBRIO_MEZZANINE-DIO53-Pad182)") (class "Default")
      (node (ref "SBRIO_MEZZANINE") (pin "182") (pinfunction "DIO53_182") (pintype "bidirectional"))
    )
    (net (code "179") (name "unconnected-(SBRIO_MEZZANINE-DIO54-Pad176)") (class "Default")
      (node (ref "SBRIO_MEZZANINE") (pin "176") (pinfunction "DIO54_176") (pintype "bidirectional"))
    )
    (net (code "180") (name "unconnected-(SBRIO_MEZZANINE-DIO55-Pad164)") (class "Default")
      (node (ref "SBRIO_MEZZANINE") (pin "164") (pinfunction "DIO55_164") (pintype "bidirectional"))
    )
    (net (code "181") (name "unconnected-(SBRIO_MEZZANINE-DIO56-Pad158)") (class "Default")
      (node (ref "SBRIO_MEZZANINE") (pin "158") (pinfunction "DIO56_158") (pintype "bidirectional"))
    )
    (net (code "182") (name "unconnected-(SBRIO_MEZZANINE-DIO57-Pad146)") (class "Default")
      (node (ref "SBRIO_MEZZANINE") (pin "146") (pinfunction "DIO57_146") (pintype "bidirectional"))
    )
    (net (code "183") (name "unconnected-(SBRIO_MEZZANINE-DIO58-Pad140)") (class "Default")
      (node (ref "SBRIO_MEZZANINE") (pin "140") (pinfunction "DIO58_140") (pintype "bidirectional"))
    )
    (net (code "184") (name "unconnected-(SBRIO_MEZZANINE-DIO59-Pad128)") (class "Default")
      (node (ref "SBRIO_MEZZANINE") (pin "128") (pinfunction "DIO59_128") (pintype "bidirectional"))
    )
    (net (code "185") (name "unconnected-(SBRIO_MEZZANINE-DIO60-Pad122)") (class "Default")
      (node (ref "SBRIO_MEZZANINE") (pin "122") (pinfunction "DIO60_122") (pintype "bidirectional"))
    )
    (net (code "186") (name "unconnected-(SBRIO_MEZZANINE-DIO61-Pad110)") (class "Default")
      (node (ref "SBRIO_MEZZANINE") (pin "110") (pinfunction "DIO61_110") (pintype "bidirectional"))
    )
    (net (code "187") (name "unconnected-(SBRIO_MEZZANINE-DIO62-Pad104)") (class "Default")
      (node (ref "SBRIO_MEZZANINE") (pin "104") (pinfunction "DIO62_104") (pintype "bidirectional"))
    )
    (net (code "188") (name "unconnected-(SBRIO_MEZZANINE-DIO63-Pad92)") (class "Default")
      (node (ref "SBRIO_MEZZANINE") (pin "92") (pinfunction "DIO63_92") (pintype "bidirectional"))
    )
    (net (code "189") (name "unconnected-(SBRIO_MEZZANINE-DIO66-Pad208)") (class "Default")
      (node (ref "SBRIO_MEZZANINE") (pin "208") (pinfunction "DIO66_208") (pintype "bidirectional"))
    )
    (net (code "190") (name "unconnected-(SBRIO_MEZZANINE-DIO67-Pad202)") (class "Default")
      (node (ref "SBRIO_MEZZANINE") (pin "202") (pinfunction "DIO67_202") (pintype "bidirectional"))
    )
    (net (code "191") (name "unconnected-(SBRIO_MEZZANINE-DIO68-Pad190)") (class "Default")
      (node (ref "SBRIO_MEZZANINE") (pin "190") (pinfunction "DIO68_190") (pintype "bidirectional"))
    )
    (net (code "192") (name "unconnected-(SBRIO_MEZZANINE-DIO69-Pad184)") (class "Default")
      (node (ref "SBRIO_MEZZANINE") (pin "184") (pinfunction "DIO69_184") (pintype "bidirectional"))
    )
    (net (code "193") (name "unconnected-(SBRIO_MEZZANINE-DIO70-Pad172)") (class "Default")
      (node (ref "SBRIO_MEZZANINE") (pin "172") (pinfunction "DIO70_172") (pintype "bidirectional"))
    )
    (net (code "194") (name "unconnected-(SBRIO_MEZZANINE-DIO71-Pad166)") (class "Default")
      (node (ref "SBRIO_MEZZANINE") (pin "166") (pinfunction "DIO71_166") (pintype "bidirectional"))
    )
    (net (code "195") (name "unconnected-(SBRIO_MEZZANINE-DIO72-Pad154)") (class "Default")
      (node (ref "SBRIO_MEZZANINE") (pin "154") (pinfunction "DIO72_154") (pintype "bidirectional"))
    )
    (net (code "196") (name "unconnected-(SBRIO_MEZZANINE-DIO73-Pad148)") (class "Default")
      (node (ref "SBRIO_MEZZANINE") (pin "148") (pinfunction "DIO73_148") (pintype "bidirectional"))
    )
    (net (code "197") (name "unconnected-(SBRIO_MEZZANINE-DIO74-Pad136)") (class "Default")
      (node (ref "SBRIO_MEZZANINE") (pin "136") (pinfunction "DIO74_136") (pintype "bidirectional"))
    )
    (net (code "198") (name "unconnected-(SBRIO_MEZZANINE-DIO75-Pad130)") (class "Default")
      (node (ref "SBRIO_MEZZANINE") (pin "130") (pinfunction "DIO75_130") (pintype "bidirectional"))
    )
    (net (code "199") (name "unconnected-(SBRIO_MEZZANINE-DIO76-Pad118)") (class "Default")
      (node (ref "SBRIO_MEZZANINE") (pin "118") (pinfunction "DIO76_118") (pintype "bidirectional"))
    )
    (net (code "200") (name "unconnected-(SBRIO_MEZZANINE-DIO77-Pad112)") (class "Default")
      (node (ref "SBRIO_MEZZANINE") (pin "112") (pinfunction "DIO77_112") (pintype "bidirectional"))
    )
    (net (code "201") (name "unconnected-(SBRIO_MEZZANINE-DIO78-Pad100)") (class "Default")
      (node (ref "SBRIO_MEZZANINE") (pin "100") (pinfunction "DIO78_100") (pintype "bidirectional"))
    )
    (net (code "202") (name "unconnected-(SBRIO_MEZZANINE-DIO79-Pad94)") (class "Default")
      (node (ref "SBRIO_MEZZANINE") (pin "94") (pinfunction "DIO79_94") (pintype "bidirectional"))
    )
    (net (code "203") (name "unconnected-(SBRIO_MEZZANINE-DIO80-Pad235)") (class "Default")
      (node (ref "SBRIO_MEZZANINE") (pin "235") (pinfunction "DIO80_235") (pintype "bidirectional"))
    )
    (net (code "204") (name "unconnected-(SBRIO_MEZZANINE-DIO82-Pad217)") (class "Default")
      (node (ref "SBRIO_MEZZANINE") (pin "217") (pinfunction "DIO82_217") (pintype "bidirectional"))
    )
    (net (code "205") (name "unconnected-(SBRIO_MEZZANINE-DIO84-Pad199)") (class "Default")
      (node (ref "SBRIO_MEZZANINE") (pin "199") (pinfunction "DIO84_199") (pintype "bidirectional"))
    )
    (net (code "206") (name "unconnected-(SBRIO_MEZZANINE-DIO89-Pad151)") (class "Default")
      (node (ref "SBRIO_MEZZANINE") (pin "151") (pinfunction "DIO89_151") (pintype "bidirectional"))
    )
    (net (code "207") (name "unconnected-(U$8-PadB)") (class "Default")
      (node (ref "U$8") (pin "B") (pinfunction "B_B") (pintype "bidirectional"))
    )
  )
)
